# BPC_PWR.net
KiCad netlist of a schematic drawn in Altium Designer
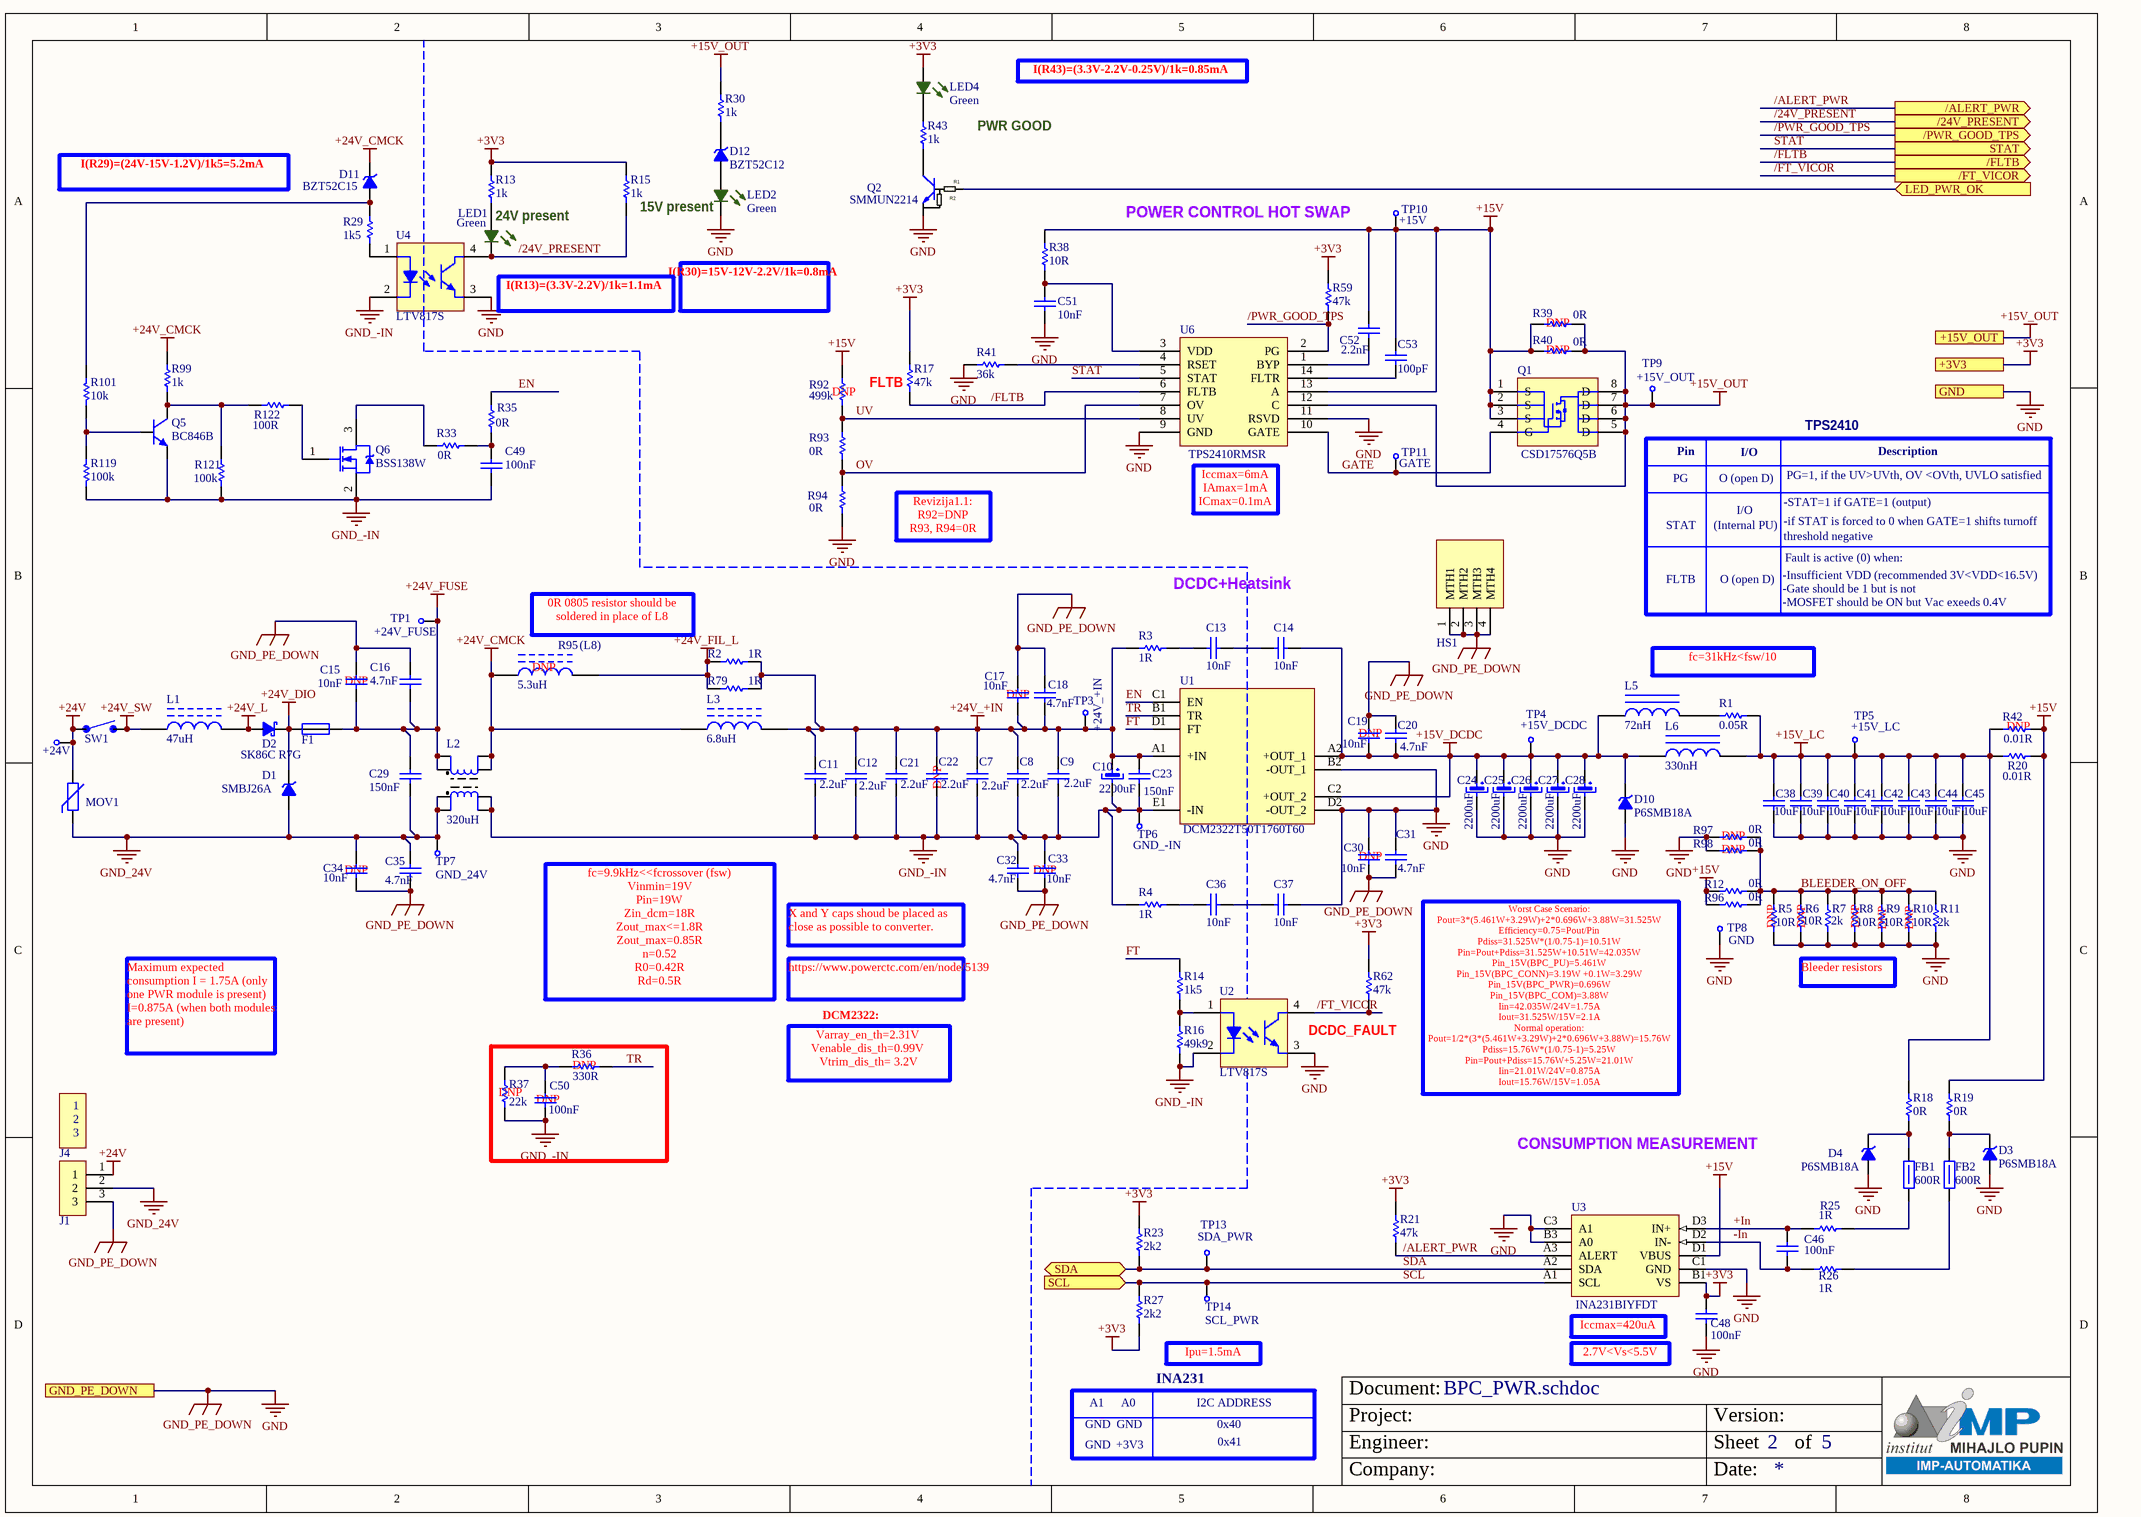
[diagram p0: BPC_PWR.schdoc]

(export (version "E")
  (design (tool "Eeschema 10.0.6"))
  (components
    (comp (ref "+24V")
      (value "Test Point Comment")
      (footprint "TP SMD 1.2mm MS")
      (description "Test Point SMD 1.2 mm No Via")
      (libsource (lib "MS IMP Library") (part "Test Point SMD"))
    )
    (comp (ref "C7")
      (value "Ceramic Capacitor")
      (footprint "2220 C 2.8MM MS")
      (description "Ceramic Capacitor 2.2uF 100V X6S 2220")
      (fields
        (field (name "DISTRIBUTOR PART NUMBER") "445-7781-1-ND")
        (field (name "MANUFACTURER") "TDK Corporation")
        (field (name "CAPACITANCE") "2.2uF")
      )
      (libsource (lib "MS IMP Library") (part "Cap Cer 2.2uF 450V X7R 2220 MS"))
    )
    (comp (ref "C8")
      (value "Ceramic Capacitor")
      (footprint "2220 C 2.8MM MS")
      (description "Ceramic Capacitor 2.2uF 100V X6S 2220")
      (fields
        (field (name "DISTRIBUTOR PART NUMBER") "445-7781-1-ND")
        (field (name "MANUFACTURER") "TDK Corporation")
        (field (name "CAPACITANCE") "2.2uF")
      )
      (libsource (lib "MS IMP Library") (part "Cap Cer 2.2uF 450V X7R 2220 MS"))
    )
    (comp (ref "C9")
      (value "Ceramic Capacitor")
      (footprint "2220 C 2.8MM MS")
      (description "Ceramic Capacitor 2.2uF 100V X6S 2220")
      (fields
        (field (name "DISTRIBUTOR PART NUMBER") "445-7781-1-ND")
        (field (name "MANUFACTURER") "TDK Corporation")
        (field (name "CAPACITANCE") "2.2uF")
      )
      (libsource (lib "MS IMP Library") (part "Cap Cer 2.2uF 450V X7R 2220 MS"))
    )
    (comp (ref "C10")
      (value "Electorlytic Capacitor")
      (footprint "CAPPRD750W85D1800H2000 MS")
      (description "Electorlytic Capacitor 2200uF 35V 18x20mm MS")
      (fields
        (field (name "DISTRIBUTOR PART NUMBER") "493-15957-ND")
        (field (name "MANUFACTURER") "Nichicon")
        (field (name "CAPACITANCE") "2200uF")
      )
      (libsource (lib "MS IMP Library") (part "Cap El 2200uF 35V 18x20mm MS"))
    )
    (comp (ref "C11")
      (value "Ceramic Capacitor")
      (footprint "2220 C 2.8MM MS")
      (description "Ceramic Capacitor 2.2uF 100V X6S 2220")
      (fields
        (field (name "DISTRIBUTOR PART NUMBER") "445-7781-1-ND")
        (field (name "MANUFACTURER") "TDK Corporation")
        (field (name "CAPACITANCE") "2.2uF")
      )
      (libsource (lib "MS IMP Library") (part "Cap Cer 2.2uF 450V X7R 2220 MS"))
    )
    (comp (ref "C12")
      (value "Ceramic Capacitor")
      (footprint "2220 C 2.8MM MS")
      (description "Ceramic Capacitor 2.2uF 100V X6S 2220")
      (fields
        (field (name "DISTRIBUTOR PART NUMBER") "445-7781-1-ND")
        (field (name "MANUFACTURER") "TDK Corporation")
        (field (name "CAPACITANCE") "2.2uF")
      )
      (libsource (lib "MS IMP Library") (part "Cap Cer 2.2uF 450V X7R 2220 MS"))
    )
    (comp (ref "C13")
      (value "Ceramic Capacitor")
      (footprint "1812 C 2.0MM MS")
      (description "Ceramic Capacitor 10nF 2kV X7R 1812")
      (fields
        (field (name "DISTRIBUTOR PART NUMBER") "399-10477-1-ND")
        (field (name "MANUFACTURER") "KEMET")
        (field (name "CAPACITANCE") "10nF")
      )
      (libsource (lib "MS IMP Library") (part "Cap Cer 10nF 2kV X7R 1812 MS"))
    )
    (comp (ref "C14")
      (value "Ceramic Capacitor")
      (footprint "1812 C 2.0MM MS")
      (description "Ceramic Capacitor 10nF 2kV X7R 1812")
      (fields
        (field (name "DISTRIBUTOR PART NUMBER") "399-10477-1-ND")
        (field (name "MANUFACTURER") "KEMET")
        (field (name "CAPACITANCE") "10nF")
      )
      (libsource (lib "MS IMP Library") (part "Cap Cer 10nF 2kV X7R 1812 MS"))
    )
    (comp (ref "C15")
      (value "Capacitor Y2")
      (footprint "R46KI21000001M")
      (description "Capacitor Y2 10nF 275V Polypropylene")
      (fields
        (field (name "DISTRIBUTOR PART NUMBER") "399-19749-ND")
        (field (name "MANUFACTURER") "Kemet")
        (field (name "POPULATED") "DNP")
        (field (name "DB PARAMETER 1") "10nF")
      )
      (libsource (lib "MS IMP Library") (part "Cap Y2 10nF 275V Polypropylene  MS"))
    )
    (comp (ref "C16")
      (value "Capacitor Y2")
      (footprint "R60QF14704001K")
      (description "Capacitor Y2 4.7nF 250V PET")
      (fields
        (field (name "DISTRIBUTOR PART NUMBER") "399-18570-ND")
        (field (name "MANUFACTURER") "Kemet")
        (field (name "DB PARAMETER 1") "4.7nF")
      )
      (libsource (lib "MS IMP Library") (part "Cap Y2 4.7nF 250V PET MS"))
    )
    (comp (ref "C17")
      (value "Capacitor Y2")
      (footprint "R46KI21000001M")
      (description "Capacitor Y2 10nF 275V Polypropylene")
      (fields
        (field (name "DISTRIBUTOR PART NUMBER") "399-19749-ND")
        (field (name "MANUFACTURER") "Kemet")
        (field (name "POPULATED") "DNP")
        (field (name "DB PARAMETER 1") "10nF")
      )
      (libsource (lib "MS IMP Library") (part "Cap Y2 10nF 275V Polypropylene  MS"))
    )
    (comp (ref "C18")
      (value "Capacitor Y2")
      (footprint "R60QF14704001K")
      (description "Capacitor Y2 4.7nF 250V PET")
      (fields
        (field (name "DISTRIBUTOR PART NUMBER") "399-18570-ND")
        (field (name "MANUFACTURER") "Kemet")
        (field (name "DB PARAMETER 1") "4.7nF")
      )
      (libsource (lib "MS IMP Library") (part "Cap Y2 4.7nF 250V PET MS"))
    )
    (comp (ref "C19")
      (value "Capacitor Y2")
      (footprint "R46KI21000001M")
      (description "Capacitor Y2 10nF 275V Polypropylene")
      (fields
        (field (name "DISTRIBUTOR PART NUMBER") "399-19749-ND")
        (field (name "MANUFACTURER") "Kemet")
        (field (name "POPULATED") "DNP")
        (field (name "DB PARAMETER 1") "10nF")
      )
      (libsource (lib "MS IMP Library") (part "Cap Y2 10nF 275V Polypropylene  MS"))
    )
    (comp (ref "C20")
      (value "Capacitor Y2")
      (footprint "R60QF14704001K")
      (description "Capacitor Y2 4.7nF 250V PET")
      (fields
        (field (name "DISTRIBUTOR PART NUMBER") "399-18570-ND")
        (field (name "MANUFACTURER") "Kemet")
        (field (name "DB PARAMETER 1") "4.7nF")
      )
      (libsource (lib "MS IMP Library") (part "Cap Y2 4.7nF 250V PET MS"))
    )
    (comp (ref "C21")
      (value "Ceramic Capacitor")
      (footprint "2220 C 2.8MM MS")
      (description "Ceramic Capacitor 2.2uF 100V X6S 2220")
      (fields
        (field (name "DISTRIBUTOR PART NUMBER") "445-7781-1-ND")
        (field (name "MANUFACTURER") "TDK Corporation")
        (field (name "CAPACITANCE") "2.2uF")
      )
      (libsource (lib "MS IMP Library") (part "Cap Cer 2.2uF 450V X7R 2220 MS"))
    )
    (comp (ref "C22")
      (value "Ceramic Capacitor")
      (footprint "2220 C 2.8MM MS")
      (description "Ceramic Capacitor 2.2uF 100V X6S 2220")
      (fields
        (field (name "DISTRIBUTOR PART NUMBER") "445-7781-1-ND")
        (field (name "MANUFACTURER") "TDK Corporation")
        (field (name "POPULATED") "DNP")
        (field (name "CAPACITANCE") "2.2uF")
      )
      (libsource (lib "MS IMP Library") (part "Cap Cer 2.2uF 450V X7R 2220 MS"))
    )
    (comp (ref "C23")
      (value "Capacitor X2")
      (footprint "MKX2 6mmx18mmx12.5mm")
      (description "Capacitor X2 150nF 305V PP")
      (fields
        (field (name "DISTRIBUTOR PART NUMBER") "505-MKX2AW31504C00KI")
        (field (name "MANUFACTURER") "WIMA")
        (field (name "DB PARAMETER 1") "150nF")
      )
      (libsource (lib "MS IMP Library") (part "Cap X2 150nF 305V PP MS"))
    )
    (comp (ref "C24")
      (value "Electorlytic Capacitor")
      (footprint "CAPPRD750W85D1800H2000 MS")
      (description "Electorlytic Capacitor 2200uF 35V 18x20mm MS")
      (fields
        (field (name "DISTRIBUTOR PART NUMBER") "493-15957-ND")
        (field (name "MANUFACTURER") "Nichicon")
        (field (name "CAPACITANCE") "2200uF")
      )
      (libsource (lib "MS IMP Library") (part "Cap El 2200uF 35V 18x20mm MS"))
    )
    (comp (ref "C25")
      (value "Electorlytic Capacitor")
      (footprint "CAPPRD750W85D1800H2000 MS")
      (description "Electorlytic Capacitor 2200uF 35V 18x20mm MS")
      (fields
        (field (name "DISTRIBUTOR PART NUMBER") "493-15957-ND")
        (field (name "MANUFACTURER") "Nichicon")
        (field (name "CAPACITANCE") "2200uF")
      )
      (libsource (lib "MS IMP Library") (part "Cap El 2200uF 35V 18x20mm MS"))
    )
    (comp (ref "C26")
      (value "Electorlytic Capacitor")
      (footprint "CAPPRD750W85D1800H2000 MS")
      (description "Electorlytic Capacitor 2200uF 35V 18x20mm MS")
      (fields
        (field (name "DISTRIBUTOR PART NUMBER") "493-15957-ND")
        (field (name "MANUFACTURER") "Nichicon")
        (field (name "CAPACITANCE") "2200uF")
      )
      (libsource (lib "MS IMP Library") (part "Cap El 2200uF 35V 18x20mm MS"))
    )
    (comp (ref "C27")
      (value "Electorlytic Capacitor")
      (footprint "CAPPRD750W85D1800H2000 MS")
      (description "Electorlytic Capacitor 2200uF 35V 18x20mm MS")
      (fields
        (field (name "DISTRIBUTOR PART NUMBER") "493-15957-ND")
        (field (name "MANUFACTURER") "Nichicon")
        (field (name "CAPACITANCE") "2200uF")
      )
      (libsource (lib "MS IMP Library") (part "Cap El 2200uF 35V 18x20mm MS"))
    )
    (comp (ref "C28")
      (value "Electorlytic Capacitor")
      (footprint "CAPPRD750W85D1800H2000 MS")
      (description "Electorlytic Capacitor 2200uF 35V 18x20mm MS")
      (fields
        (field (name "DISTRIBUTOR PART NUMBER") "493-15957-ND")
        (field (name "MANUFACTURER") "Nichicon")
        (field (name "CAPACITANCE") "2200uF")
      )
      (libsource (lib "MS IMP Library") (part "Cap El 2200uF 35V 18x20mm MS"))
    )
    (comp (ref "C29")
      (value "Capacitor X2")
      (footprint "MKX2 6mmx18mmx12.5mm")
      (description "Capacitor X2 150nF 305V PP")
      (fields
        (field (name "DISTRIBUTOR PART NUMBER") "505-MKX2AW31504C00KI")
        (field (name "MANUFACTURER") "WIMA")
        (field (name "DB PARAMETER 1") "150nF")
      )
      (libsource (lib "MS IMP Library") (part "Cap X2 150nF 305V PP MS"))
    )
    (comp (ref "C30")
      (value "Capacitor Y2")
      (footprint "R46KI21000001M")
      (description "Capacitor Y2 10nF 275V Polypropylene")
      (fields
        (field (name "DISTRIBUTOR PART NUMBER") "399-19749-ND")
        (field (name "MANUFACTURER") "Kemet")
        (field (name "POPULATED") "DNP")
        (field (name "DB PARAMETER 1") "10nF")
      )
      (libsource (lib "MS IMP Library") (part "Cap Y2 10nF 275V Polypropylene  MS"))
    )
    (comp (ref "C31")
      (value "Capacitor Y2")
      (footprint "R60QF14704001K")
      (description "Capacitor Y2 4.7nF 250V PET")
      (fields
        (field (name "DISTRIBUTOR PART NUMBER") "399-18570-ND")
        (field (name "MANUFACTURER") "Kemet")
        (field (name "DB PARAMETER 1") "4.7nF")
      )
      (libsource (lib "MS IMP Library") (part "Cap Y2 4.7nF 250V PET MS"))
    )
    (comp (ref "C32")
      (value "Capacitor Y2")
      (footprint "R60QF14704001K")
      (description "Capacitor Y2 4.7nF 250V PET")
      (fields
        (field (name "DISTRIBUTOR PART NUMBER") "399-18570-ND")
        (field (name "MANUFACTURER") "Kemet")
        (field (name "DB PARAMETER 1") "4.7nF")
      )
      (libsource (lib "MS IMP Library") (part "Cap Y2 4.7nF 250V PET MS"))
    )
    (comp (ref "C33")
      (value "Capacitor Y2")
      (footprint "R46KI21000001M")
      (description "Capacitor Y2 10nF 275V Polypropylene")
      (fields
        (field (name "DISTRIBUTOR PART NUMBER") "399-19749-ND")
        (field (name "MANUFACTURER") "Kemet")
        (field (name "POPULATED") "DNP")
        (field (name "DB PARAMETER 1") "10nF")
      )
      (libsource (lib "MS IMP Library") (part "Cap Y2 10nF 275V Polypropylene  MS"))
    )
    (comp (ref "C34")
      (value "Capacitor Y2")
      (footprint "R46KI21000001M")
      (description "Capacitor Y2 10nF 275V Polypropylene")
      (fields
        (field (name "DISTRIBUTOR PART NUMBER") "399-19749-ND")
        (field (name "MANUFACTURER") "Kemet")
        (field (name "POPULATED") "DNP")
        (field (name "DB PARAMETER 1") "10nF")
      )
      (libsource (lib "MS IMP Library") (part "Cap Y2 10nF 275V Polypropylene  MS"))
    )
    (comp (ref "C35")
      (value "Capacitor Y2")
      (footprint "R60QF14704001K")
      (description "Capacitor Y2 4.7nF 250V PET")
      (fields
        (field (name "DISTRIBUTOR PART NUMBER") "399-18570-ND")
        (field (name "MANUFACTURER") "Kemet")
        (field (name "DB PARAMETER 1") "4.7nF")
      )
      (libsource (lib "MS IMP Library") (part "Cap Y2 4.7nF 250V PET MS"))
    )
    (comp (ref "C36")
      (value "Ceramic Capacitor")
      (footprint "1812 C 2.0MM MS")
      (description "Ceramic Capacitor 10nF 2kV X7R 1812")
      (fields
        (field (name "DISTRIBUTOR PART NUMBER") "399-10477-1-ND")
        (field (name "MANUFACTURER") "KEMET")
        (field (name "CAPACITANCE") "10nF")
      )
      (libsource (lib "MS IMP Library") (part "Cap Cer 10nF 2kV X7R 1812 MS"))
    )
    (comp (ref "C37")
      (value "Ceramic Capacitor")
      (footprint "1812 C 2.0MM MS")
      (description "Ceramic Capacitor 10nF 2kV X7R 1812")
      (fields
        (field (name "DISTRIBUTOR PART NUMBER") "399-10477-1-ND")
        (field (name "MANUFACTURER") "KEMET")
        (field (name "CAPACITANCE") "10nF")
      )
      (libsource (lib "MS IMP Library") (part "Cap Cer 10nF 2kV X7R 1812 MS"))
    )
    (comp (ref "C38")
      (value "Ceramic Capacitor")
      (footprint "2220 C 2.8MM MS")
      (description "Ceramic Capacitor 10uF 100V X7S 2220")
      (fields
        (field (name "DISTRIBUTOR PART NUMBER") "445-13408-1-ND")
        (field (name "MANUFACTURER") "TDK Corporation")
        (field (name "CAPACITANCE") "10uF")
      )
      (libsource (lib "MS IMP Library") (part "Cap Cer 10uF 100V X7S 2220 MS"))
    )
    (comp (ref "C39")
      (value "Ceramic Capacitor")
      (footprint "2220 C 2.8MM MS")
      (description "Ceramic Capacitor 10uF 100V X7S 2220")
      (fields
        (field (name "DISTRIBUTOR PART NUMBER") "445-13408-1-ND")
        (field (name "MANUFACTURER") "TDK Corporation")
        (field (name "CAPACITANCE") "10uF")
      )
      (libsource (lib "MS IMP Library") (part "Cap Cer 10uF 100V X7S 2220 MS"))
    )
    (comp (ref "C40")
      (value "Ceramic Capacitor")
      (footprint "2220 C 2.8MM MS")
      (description "Ceramic Capacitor 10uF 100V X7S 2220")
      (fields
        (field (name "DISTRIBUTOR PART NUMBER") "445-13408-1-ND")
        (field (name "MANUFACTURER") "TDK Corporation")
        (field (name "CAPACITANCE") "10uF")
      )
      (libsource (lib "MS IMP Library") (part "Cap Cer 10uF 100V X7S 2220 MS"))
    )
    (comp (ref "C41")
      (value "Ceramic Capacitor")
      (footprint "2220 C 2.8MM MS")
      (description "Ceramic Capacitor 10uF 100V X7S 2220")
      (fields
        (field (name "DISTRIBUTOR PART NUMBER") "445-13408-1-ND")
        (field (name "MANUFACTURER") "TDK Corporation")
        (field (name "CAPACITANCE") "10uF")
      )
      (libsource (lib "MS IMP Library") (part "Cap Cer 10uF 100V X7S 2220 MS"))
    )
    (comp (ref "C42")
      (value "Ceramic Capacitor")
      (footprint "2220 C 2.8MM MS")
      (description "Ceramic Capacitor 10uF 100V X7S 2220")
      (fields
        (field (name "DISTRIBUTOR PART NUMBER") "445-13408-1-ND")
        (field (name "MANUFACTURER") "TDK Corporation")
        (field (name "CAPACITANCE") "10uF")
      )
      (libsource (lib "MS IMP Library") (part "Cap Cer 10uF 100V X7S 2220 MS"))
    )
    (comp (ref "C43")
      (value "Ceramic Capacitor")
      (footprint "2220 C 2.8MM MS")
      (description "Ceramic Capacitor 10uF 100V X7S 2220")
      (fields
        (field (name "DISTRIBUTOR PART NUMBER") "445-13408-1-ND")
        (field (name "MANUFACTURER") "TDK Corporation")
        (field (name "CAPACITANCE") "10uF")
      )
      (libsource (lib "MS IMP Library") (part "Cap Cer 10uF 100V X7S 2220 MS"))
    )
    (comp (ref "C44")
      (value "Ceramic Capacitor")
      (footprint "2220 C 2.8MM MS")
      (description "Ceramic Capacitor 10uF 100V X7S 2220")
      (fields
        (field (name "DISTRIBUTOR PART NUMBER") "445-13408-1-ND")
        (field (name "MANUFACTURER") "TDK Corporation")
        (field (name "CAPACITANCE") "10uF")
      )
      (libsource (lib "MS IMP Library") (part "Cap Cer 10uF 100V X7S 2220 MS"))
    )
    (comp (ref "C45")
      (value "Ceramic Capacitor")
      (footprint "2220 C 2.8MM MS")
      (description "Ceramic Capacitor 10uF 100V X7S 2220")
      (fields
        (field (name "DISTRIBUTOR PART NUMBER") "445-13408-1-ND")
        (field (name "MANUFACTURER") "TDK Corporation")
        (field (name "CAPACITANCE") "10uF")
      )
      (libsource (lib "MS IMP Library") (part "Cap Cer 10uF 100V X7S 2220 MS"))
    )
    (comp (ref "C46")
      (value "Ceramic Capacitor")
      (footprint "C0603L 0.8 MM MS")
      (description "Ceramic Capacitor 100nF 50V X7R 0603")
      (fields
        (field (name "DISTRIBUTOR PART NUMBER") "187-CL10B104KB8WPNC")
        (field (name "MANUFACTURER") "Samsung Electro-Mechanics")
        (field (name "CAPACITANCE") "100nF")
      )
      (libsource (lib "MS IMP Library") (part "Cap Cer 100nF 50V X7R 0603 Pt02"))
    )
    (comp (ref "C48")
      (value "Ceramic Capacitor")
      (footprint "C0603L 0.8 MM MS")
      (description "Ceramic Capacitor 100nF 50V X7R 0603")
      (fields
        (field (name "DISTRIBUTOR PART NUMBER") "187-CL10B104KB8WPNC")
        (field (name "MANUFACTURER") "Samsung Electro-Mechanics")
        (field (name "CAPACITANCE") "100nF")
      )
      (libsource (lib "MS IMP Library") (part "Cap Cer 100nF 50V X7R 0603 Pt02"))
    )
    (comp (ref "C49")
      (value "Ceramic Capacitor")
      (footprint "C0603L 0.8 MM MS")
      (description "Ceramic Capacitor 100nF 50V X7R 0603")
      (fields
        (field (name "DISTRIBUTOR PART NUMBER") "187-CL10B104KB8WPNC")
        (field (name "MANUFACTURER") "Samsung Electro-Mechanics")
        (field (name "CAPACITANCE") "100nF")
      )
      (libsource (lib "MS IMP Library") (part "Cap Cer 100nF 50V X7R 0603 Pt02"))
    )
    (comp (ref "C50")
      (value "Ceramic Capacitor")
      (footprint "C0603L 0.8 MM MS")
      (description "Ceramic Capacitor 100nF 50V X7R 0603")
      (fields
        (field (name "DISTRIBUTOR PART NUMBER") "187-CL10B104KB8WPNC")
        (field (name "MANUFACTURER") "Samsung Electro-Mechanics")
        (field (name "PRODUCTION STATUS") "DNP")
        (field (name "CAPACITANCE") "100nF")
      )
      (libsource (lib "MS IMP Library") (part "Cap Cer 100nF 50V X7R 0603 Pt02"))
    )
    (comp (ref "C51")
      (value "Ceramic Capacitor")
      (footprint "C0603L 0.8 MM MS")
      (description "Ceramic Capacitor 10nF 50V X7R 0603")
      (fields
        (field (name "DISTRIBUTOR PART NUMBER") "445-5662-1-ND")
        (field (name "MANUFACTURER") "TDK Corporation")
        (field (name "CAPACITANCE") "10nF")
      )
      (libsource (lib "MS IMP Library") (part "Cap Cer 10nF 50V X7R 0603 MS"))
    )
    (comp (ref "C52")
      (value "Ceramic Capacitor")
      (footprint "C0603L 0.8 MM MS")
      (description "Ceramic Capacitor 2.2nF 100V X7R 0603")
      (fields
        (field (name "DISTRIBUTOR PART NUMBER") "445-5808-1-ND")
        (field (name "MANUFACTURER") "TDK Corporation")
        (field (name "CAPACITANCE") "2.2nF")
      )
      (libsource (lib "MS IMP Library") (part "Cap Cer 2.2nF 100V X7R 0603 MS"))
    )
    (comp (ref "C53")
      (value "Ceramic Capacitor")
      (footprint "C0603L 0.8 MM MS")
      (description "Ceramic Capacitor 100pF 100V X7R 0603")
      (fields
        (field (name "DISTRIBUTOR PART NUMBER") "478-12671-1-ND")
        (field (name "MANUFACTURER") "AVX Corporation")
        (field (name "CAPACITANCE") "100pF")
      )
      (libsource (lib "MS IMP Library") (part "Cap Cer 100pF 100V X7R 0603 MS"))
    )
    (comp (ref "D1")
      (value "SMBJ26A")
      (footprint "DO-214AA SMB MS")
      (description "TVS Diode 26V 600W Unidirectional")
      (fields (field (name "DISTRIBUTOR PART NUMBER") "SMBJ26ABCT-ND") (field (name "MANUFACTURER") "Bourns"))
      (libsource (lib "MS IMP Library") (part "Dio TVS Udir 26V 600W SMBJ26A MS"))
    )
    (comp (ref "D2")
      (value "SK86C R7G")
      (footprint "DIOM7959X262N")
      (description "Schottky Diode 8A 60V SMC")
      (fields
        (field (name "DISTRIBUTOR PART NUMBER") "SK86CR7GCT-ND")
        (field (name "MANUFACTURER") "Taiwan Semiconductor Corporation")
      )
      (libsource (lib "MS IMP Library") (part "Dio Sch 8A 60V SMC MS"))
    )
    (comp (ref "D3")
      (value "P6SMB18A")
      (footprint "DO-214AA SMB MS")
      (description "TVS Diode 15.3V 600W Unidirectional")
      (fields
        (field (name "DISTRIBUTOR PART NUMBER") "P6SMB18ABBCT-ND")
        (field (name "MANUFACTURER") "Bourns")
      )
      (libsource (lib "MS IMP Library") (part "Dio TVS Udir 15.3V 600W P6SMB18A MS"))
    )
    (comp (ref "D4")
      (value "P6SMB18A")
      (footprint "DO-214AA SMB MS")
      (description "TVS Diode 15.3V 600W Unidirectional")
      (fields
        (field (name "DISTRIBUTOR PART NUMBER") "P6SMB18ABBCT-ND")
        (field (name "MANUFACTURER") "Bourns")
      )
      (libsource (lib "MS IMP Library") (part "Dio TVS Udir 15.3V 600W P6SMB18A MS"))
    )
    (comp (ref "D10")
      (value "P6SMB18A")
      (footprint "DO-214AA SMB MS")
      (description "TVS Diode 15.3V 600W Unidirectional")
      (fields
        (field (name "DISTRIBUTOR PART NUMBER") "P6SMB18ABBCT-ND")
        (field (name "MANUFACTURER") "Bourns")
      )
      (libsource (lib "MS IMP Library") (part "Dio TVS Udir 15.3V 600W P6SMB18A MS"))
    )
    (comp (ref "D11")
      (value "BZT52C15")
      (footprint "SOD-123 MS")
      (description "Zener Diode 15V 500mW")
      (fields
        (field (name "DISTRIBUTOR PART NUMBER") "637-BZT52C15")
        (field (name "MANUFACTURER") "Diotec Semiconductor")
      )
      (libsource (lib "MS IMP Library") (part "Dio Zen 15V 500mW BZT52C15S  MS"))
    )
    (comp (ref "D12")
      (value "BZT52C12")
      (footprint "SOD-123 MS")
      (description "Zener Diode 12V 500mW")
      (fields
        (field (name "DISTRIBUTOR PART NUMBER") "621-BZT52C12-F")
        (field (name "MANUFACTURER") "Diodes Inc.")
      )
      (libsource (lib "MS IMP Library") (part "Dio Zen 12V 500mW BZT52C12 MS"))
    )
    (comp (ref "F1")
      (value "FUSEHOLDER")
      (footprint "FUSEHOLDER_00318221")
      (description "FUSEHOLDER 10A 500V")
      (fields
        (field (name "DISTRIBUTOR PART NUMBER") "486-1260-ND")
        (field (name "MANUFACTURER") "Schurter Inc.")
      )
      (libsource (lib "MS IMP Library") (part "FUSEHOLDER"))
    )
    (comp (ref "FB1")
      (value "Ferrite Bead")
      (footprint "0805 FB 0.85mm MS")
      (description "Ferrite Bead 2A 600R@100MHz 0805")
      (fields
        (field (name "DISTRIBUTOR PART NUMBER") "490-18588-1-ND")
        (field (name "MANUFACTURER") "Murata Electronics")
        (field (name "IMPEDANCE @ 100MHZ") "600R")
      )
      (libsource (lib "MS IMP Library") (part "FB 2A 600R 0805 Pt02 MS"))
    )
    (comp (ref "FB2")
      (value "Ferrite Bead")
      (footprint "0805 FB 0.85mm MS")
      (description "Ferrite Bead 2A 600R@100MHz 0805")
      (fields
        (field (name "DISTRIBUTOR PART NUMBER") "490-18588-1-ND")
        (field (name "MANUFACTURER") "Murata Electronics")
        (field (name "IMPEDANCE @ 100MHZ") "600R")
      )
      (libsource (lib "MS IMP Library") (part "FB 2A 600R 0805 Pt02 MS"))
    )
    (comp (ref "HS1")
      (value "Heatsink")
      (footprint "Heatsink VICOR Tranverse Grounding Tabs Thermal 40138")
      (description "Heatsink Vicor Transverse 40138")
      (fields (field (name "DISTRIBUTOR PART NUMBER") "40138") (field (name "MANUFACTURER") "Vicor"))
      (libsource (lib "MS IMP Library") (part "Mech Heatsink Vicor Transverse 40138"))
    )
    (comp (ref "J1")
      (value "Header Male TH 3-pin")
      (footprint "MSTB 2,5_3-GF-5,08 - 1776511")
      (description "Con Header 1x3 5.08 12A")
      (fields
        (field (name "DISTRIBUTOR PART NUMBER") "277-5772-ND")
        (field (name "MANUFACTURER") "Phoenix Contact")
      )
      (libsource (lib "MS IMP Library") (part "Con Header 1x3 5.08 Phoenix MS"))
    )
    (comp (ref "J4")
      (value "Header Male TH 3-pin")
      (footprint "MSTB 2,5/ 3-STF-5,08 - 1777992")
      (description "Con Header 1x3 5.08 12A")
      (fields
        (field (name "DISTRIBUTOR PART NUMBER") "277-5712-ND")
        (field (name "MANUFACTURER") "Phoenix Contact")
      )
      (libsource (lib "MS IMP Library") (part "Mech Con Cable 1x3 5.08 Phoenix MS"))
    )
    (comp (ref "L1")
      (value "Inductor")
      (footprint "SER1390153MLB")
      (description "Inductor 47uH 2.6A 2.31 MOHM")
      (fields
        (field (name "DISTRIBUTOR PART NUMBER") "994-SER1390-473MLB")
        (field (name "MANUFACTURER") "Coilcraft")
        (field (name "INDUCTANCE") "47uH")
      )
      (libsource (lib "MS IMP Library") (part "Ind  47uH 2.6A SER1390"))
    )
    (comp (ref "L2")
      (value "Inductor Common Mode Choke")
      (footprint "WE-UCF")
      (description "Inductor 320uH 3.25A 744290321")
      (fields
        (field (name "DISTRIBUTOR PART NUMBER") "732-5616-1-ND")
        (field (name "MANUFACTURER") "Würth Elektronik")
        (field (name "INDUCTANCE") "320uH")
      )
      (libsource (lib "MS IMP Library") (part "Ind CMC 320µH  3.25A 744290321 MS"))
    )
    (comp (ref "L3")
      (value "Inductor")
      (footprint "INDPM110100X400N_MSS1048")
      (description "Inductor 6.8uH 6.01A 15.4 MOHM")
      (fields
        (field (name "DISTRIBUTOR PART NUMBER") "994-MSS1048-682NLC")
        (field (name "MANUFACTURER") "Coilcraft")
        (field (name "INDUCTANCE") "6.8uH")
      )
      (libsource (lib "MS IMP Library") (part "Ind  6.8uH 6.01A MSS1048 MS"))
    )
    (comp (ref "L5")
      (value "Inductor")
      (footprint "IFLR2727")
      (description "Inductor 72nH 45A IFLR2727")
      (fields
        (field (name "DISTRIBUTOR PART NUMBER") "541-3104-1-ND")
        (field (name "MANUFACTURER") "Vishay Dale")
        (field (name "INDUCTANCE") "72nH")
      )
      (libsource (lib "MS IMP Library") (part "Ind 72nH 45A IFLR2727 MS"))
    )
    (comp (ref "L6")
      (value "Inductor")
      (footprint "IHLP3232")
      (description "Inductor 330nH 29.5A IHLP3232")
      (fields
        (field (name "DISTRIBUTOR PART NUMBER") "541-1379-1-ND")
        (field (name "MANUFACTURER") "Vishay Dale")
        (field (name "INDUCTANCE") "330nH")
      )
      (libsource (lib "MS IMP Library") (part "Ind 330nH 29.5A IHLP3232 MS"))
    )
    (comp (ref "LED1")
      (value "Green")
      (footprint "LED GRN Mentor 2632.8380 x1")
      (description "LED Mentor 2632.8320 GRN x1")
      (fields
        (field (name "DISTRIBUTOR PART NUMBER") "2632.8380")
        (field (name "MANUFACTURER") "Mentor")
        (field (name "LED COLOR") "Green")
      )
      (libsource (lib "MS IMP Library") (part "LED Mentor 2632.8380 GRN x1 MS"))
    )
    (comp (ref "LED2")
      (value "Green")
      (footprint "LED GRN Mentor 2632.8380 x1")
      (description "LED Mentor 2632.8320 GRN x1")
      (fields
        (field (name "DISTRIBUTOR PART NUMBER") "2632.8380")
        (field (name "MANUFACTURER") "Mentor")
        (field (name "LED COLOR") "Green")
      )
      (libsource (lib "MS IMP Library") (part "LED Mentor 2632.8380 GRN x1 MS"))
    )
    (comp (ref "LED4")
      (value "Green")
      (footprint "LED GRN Mentor 2632.8380 x1")
      (description "LED Mentor 2632.8320 GRN x1")
      (fields
        (field (name "DISTRIBUTOR PART NUMBER") "2632.8380")
        (field (name "MANUFACTURER") "Mentor")
        (field (name "LED COLOR") "Green")
      )
      (libsource (lib "MS IMP Library") (part "LED Mentor 2632.8380 GRN x1 MS"))
    )
    (comp (ref "MOV1")
      (value "Varistor")
      (footprint "MOV10D470K")
      (description "Varistor 47V 500A DISC 10MM")
      (fields
        (field (name "DISTRIBUTOR PART NUMBER") "MOV-10D470KTRCT-ND")
        (field (name "MANUFACTURER") "Bourns Inc.")
      )
      (libsource (lib "MS IMP Library") (part "MOV 47V 5.5J 10D470K"))
    )
    (comp (ref "Q1")
      (value "CSD17576Q5B")
      (footprint "DNK8 MS")
      (description "MOSFET N-CH 30V 100A 8VSON")
      (fields
        (field (name "DISTRIBUTOR PART NUMBER") "296-43635-1-ND")
        (field (name "MANUFACTURER") "Texas Instruments")
      )
      (libsource (lib "MS IMP Library") (part "Tr CSD17576Q5B MS"))
    )
    (comp (ref "Q2")
      (value "SMMUN2214")
      (footprint "SOT-23 MS")
      (description "TRANS PREBIAS NPN 50V SOT23")
      (fields
        (field (name "DISTRIBUTOR PART NUMBER") "SMMUN2214LT1GOSCT-ND")
        (field (name "MANUFACTURER") "ON Semiconductor")
      )
      (libsource (lib "MS IMP Library") (part "Tra NPN Prebias MS"))
    )
    (comp (ref "Q5")
      (value "BC846B")
      (footprint "SOT-23 NXP MS")
      (description "65V, 100mA NPN general-purpose transistor")
      (fields
        (field (name "DISTRIBUTOR PART NUMBER") "771-BC846B-T/R")
        (field (name "MANUFACTURER") "Nexperia")
      )
      (libsource (lib "MS IMP Library") (part "Tra NPN BC846B MS"))
    )
    (comp (ref "Q6")
      (value "BSS138W")
      (footprint "SOT65P210X110-3N")
      (description "MOSFET N-CH 50V 210MA SC70")
      (fields
        (field (name "DISTRIBUTOR PART NUMBER") "BSS138WCT-ND")
        (field (name "MANUFACTURER") "ON Semiconductor")
      )
      (libsource (lib "MS IMP Library") (part "Tra N-CH BSS138W MS"))
    )
    (comp (ref "R1")
      (value "Resistor")
      (footprint "2512 R 0.7mm MS")
      (description "Resistor 0.05R 1% 1W 2512")
      (fields
        (field (name "DISTRIBUTOR PART NUMBER") "311-0.05TCT-ND")
        (field (name "MANUFACTURER") "Yageo")
        (field (name "RESISTANCE") "0.05R")
      )
      (libsource (lib "MS IMP Library") (part "Res 0.05R 1% 1W 2512 MS"))
    )
    (comp (ref "R2")
      (value "Resistor")
      (footprint "2512 R 0.7mm MS")
      (description "Resistor 1R 5% 1W 2512")
      (fields
        (field (name "DISTRIBUTOR PART NUMBER") "2019-SR733ATTE1R00FCT-ND")
        (field (name "MANUFACTURER") "KOA Speer Electronics, Inc.")
        (field (name "RESISTANCE") "1R")
      )
      (libsource (lib "MS IMP Library") (part "Res 1R 5% 1W 2512 MS"))
    )
    (comp (ref "R3")
      (value "Resistor")
      (footprint "2512 R 0.7mm MS")
      (description "Resistor 1R 5% 1W 2512")
      (fields
        (field (name "DISTRIBUTOR PART NUMBER") "2019-SR733ATTE1R00FCT-ND")
        (field (name "MANUFACTURER") "KOA Speer Electronics, Inc.")
        (field (name "RESISTANCE") "1R")
      )
      (libsource (lib "MS IMP Library") (part "Res 1R 5% 1W 2512 MS"))
    )
    (comp (ref "R4")
      (value "Resistor")
      (footprint "2512 R 0.7mm MS")
      (description "Resistor 1R 5% 1W 2512")
      (fields
        (field (name "DISTRIBUTOR PART NUMBER") "2019-SR733ATTE1R00FCT-ND")
        (field (name "MANUFACTURER") "KOA Speer Electronics, Inc.")
        (field (name "RESISTANCE") "1R")
      )
      (libsource (lib "MS IMP Library") (part "Res 1R 5% 1W 2512 MS"))
    )
    (comp (ref "R5")
      (value "Resistor")
      (footprint "2512 R 0.7mm MS")
      (description "Resistor 10R 5% 2W 2512 MS")
      (fields
        (field (name "DISTRIBUTOR PART NUMBER") "YAG5928CT-ND")
        (field (name "MANUFACTURER") "Yageo")
        (field (name "POPULATED") "DNP")
        (field (name "RESISTANCE") "10R")
      )
      (libsource (lib "MS IMP Library") (part "Res 10R 5% 2W 2512 MS"))
    )
    (comp (ref "R6")
      (value "Resistor")
      (footprint "2512 R 0.7mm MS")
      (description "Resistor 10R 5% 2W 2512 MS")
      (fields
        (field (name "DISTRIBUTOR PART NUMBER") "YAG5928CT-ND")
        (field (name "MANUFACTURER") "Yageo")
        (field (name "POPULATED") "DNP")
        (field (name "RESISTANCE") "10R")
      )
      (libsource (lib "MS IMP Library") (part "Res 10R 5% 2W 2512 MS"))
    )
    (comp (ref "R7")
      (value "Resistor")
      (footprint "2512 R 0.7mm MS")
      (description "Resistor 2k 1% 2W 2512 MS")
      (fields
        (field (name "DISTRIBUTOR PART NUMBER") "279-35212K0FT")
        (field (name "MANUFACTURER") "TE Connectivity / Holsworthy")
        (field (name "RESISTANCE") "2k")
      )
      (libsource (lib "MS IMP Library") (part "Res 2k 1% 2W 2512 MS"))
    )
    (comp (ref "R8")
      (value "Resistor")
      (footprint "2512 R 0.7mm MS")
      (description "Resistor 10R 5% 2W 2512 MS")
      (fields
        (field (name "DISTRIBUTOR PART NUMBER") "YAG5928CT-ND")
        (field (name "MANUFACTURER") "Yageo")
        (field (name "POPULATED") "DNP")
        (field (name "RESISTANCE") "10R")
      )
      (libsource (lib "MS IMP Library") (part "Res 10R 5% 2W 2512 MS"))
    )
    (comp (ref "R9")
      (value "Resistor")
      (footprint "2512 R 0.7mm MS")
      (description "Resistor 10R 5% 2W 2512 MS")
      (fields
        (field (name "DISTRIBUTOR PART NUMBER") "YAG5928CT-ND")
        (field (name "MANUFACTURER") "Yageo")
        (field (name "POPULATED") "DNP")
        (field (name "RESISTANCE") "10R")
      )
      (libsource (lib "MS IMP Library") (part "Res 10R 5% 2W 2512 MS"))
    )
    (comp (ref "R10")
      (value "Resistor")
      (footprint "2512 R 0.7mm MS")
      (description "Resistor 10R 5% 2W 2512 MS")
      (fields
        (field (name "DISTRIBUTOR PART NUMBER") "YAG5928CT-ND")
        (field (name "MANUFACTURER") "Yageo")
        (field (name "POPULATED") "DNP")
        (field (name "RESISTANCE") "10R")
      )
      (libsource (lib "MS IMP Library") (part "Res 10R 5% 2W 2512 MS"))
    )
    (comp (ref "R11")
      (value "Resistor")
      (footprint "2512 R 0.7mm MS")
      (description "Resistor 2k 1% 2W 2512 MS")
      (fields
        (field (name "DISTRIBUTOR PART NUMBER") "279-35212K0FT")
        (field (name "MANUFACTURER") "TE Connectivity / Holsworthy")
        (field (name "RESISTANCE") "2k")
      )
      (libsource (lib "MS IMP Library") (part "Res 2k 1% 2W 2512 MS"))
    )
    (comp (ref "R12")
      (value "Resistor")
      (footprint "R0603L 0.45MM MS")
      (description "Resistor  0R 100mW 0603")
      (fields
        (field (name "DISTRIBUTOR PART NUMBER") "RMCF0603ZT0R00CT-ND")
        (field (name "MANUFACTURER") "Stackpole Electronics Inc")
        (field (name "RESISTANCE") "0R")
      )
      (libsource (lib "MS IMP Library") (part "Res 0R 100mW 0603"))
    )
    (comp (ref "R13")
      (value "Resistor")
      (footprint "R0603L 0.45MM MS")
      (description "Resistor 1k 1% 125mW 0603")
      (fields
        (field (name "DISTRIBUTOR PART NUMBER") "MCT0603-1.00K-CFCT-ND")
        (field (name "MANUFACTURER") "Vishay Beyschlag/Draloric/BC Components")
        (field (name "RESISTANCE") "1k")
      )
      (libsource (lib "MS IMP Library") (part "Res 1k 1% 125mW 0603"))
    )
    (comp (ref "R14")
      (value "Resistor")
      (footprint "R0603L 0.45MM MS")
      (description "Resistor 1k5 1% 100mW 0603")
      (fields
        (field (name "DISTRIBUTOR PART NUMBER") "541-4020-1-ND")
        (field (name "MANUFACTURER") "Vishay Dale")
        (field (name "RESISTANCE") "1k5")
      )
      (libsource (lib "MS IMP Library") (part "Res 1k5 1% 100mW 0603 MS"))
    )
    (comp (ref "R15")
      (value "Resistor")
      (footprint "R0603L 0.45MM MS")
      (description "Resistor 1k 1% 125mW 0603")
      (fields
        (field (name "DISTRIBUTOR PART NUMBER") "MCT0603-1.00K-CFCT-ND")
        (field (name "MANUFACTURER") "Vishay Beyschlag/Draloric/BC Components")
        (field (name "RESISTANCE") "1k")
      )
      (libsource (lib "MS IMP Library") (part "Res 1k 1% 125mW 0603"))
    )
    (comp (ref "R16")
      (value "Resistor")
      (footprint "R0603L 0.45MM MS")
      (description "Resistor 49k9 1% 100mW 0603")
      (fields
        (field (name "DISTRIBUTOR PART NUMBER") "311-49.9KHRCT-ND")
        (field (name "MANUFACTURER") "Yageo")
        (field (name "RESISTANCE") "49k9")
      )
      (libsource (lib "MS IMP Library") (part "Res 49k9 1% 100mW 0603"))
    )
    (comp (ref "R17")
      (value "Resistor")
      (footprint "R0603L 0.45MM MS")
      (description "Resistor 47k 1% 100mW 0603")
      (fields
        (field (name "DISTRIBUTOR PART NUMBER") "YAG3355CT-ND")
        (field (name "MANUFACTURER") "Yageo")
        (field (name "RESISTANCE") "47k")
      )
      (libsource (lib "MS IMP Library") (part "Res 47k 1% 100mW 0603 MS"))
    )
    (comp (ref "R18")
      (value "Resistor")
      (footprint "0805 R 0.5mm MS")
      (description "Resistor  0R 125mW 0805")
      (fields
        (field (name "DISTRIBUTOR PART NUMBER") "311-0.0ARCT-ND")
        (field (name "MANUFACTURER") "Yageo")
        (field (name "RESISTANCE") "0R")
      )
      (libsource (lib "MS IMP Library") (part "Res 0R 125mW 0805"))
    )
    (comp (ref "R19")
      (value "Resistor")
      (footprint "0805 R 0.5mm MS")
      (description "Resistor  0R 125mW 0805")
      (fields
        (field (name "DISTRIBUTOR PART NUMBER") "311-0.0ARCT-ND")
        (field (name "MANUFACTURER") "Yageo")
        (field (name "RESISTANCE") "0R")
      )
      (libsource (lib "MS IMP Library") (part "Res 0R 125mW 0805"))
    )
    (comp (ref "R20")
      (value "Resistor")
      (footprint "2512 R 0.7mm MS")
      (description "Resistor 0.01R 1% 2W 2512")
      (fields
        (field (name "DISTRIBUTOR PART NUMBER") "YAG6033CT-ND")
        (field (name "MANUFACTURER") "Yageo")
        (field (name "RESISTANCE") "0.01R")
      )
      (libsource (lib "MS IMP Library") (part "Res 0.01R 1% 2W 2512 MS"))
    )
    (comp (ref "R21")
      (value "Resistor")
      (footprint "R0603L 0.45MM MS")
      (description "Resistor 47k 1% 100mW 0603")
      (fields
        (field (name "DISTRIBUTOR PART NUMBER") "YAG3355CT-ND")
        (field (name "MANUFACTURER") "Yageo")
        (field (name "RESISTANCE") "47k")
      )
      (libsource (lib "MS IMP Library") (part "Res 47k 1% 100mW 0603 MS"))
    )
    (comp (ref "R23")
      (value "Resistor")
      (footprint "R0603L 0.45MM MS")
      (description "Resistor 2k2 1% 100mW 0603")
      (fields
        (field (name "DISTRIBUTOR PART NUMBER") "311-2.20KHRCT-ND")
        (field (name "MANUFACTURER") "Yageo")
        (field (name "RESISTANCE") "2k2")
      )
      (libsource (lib "MS IMP Library") (part "Res 2k2 1% 100mW 0603 MS Pt02"))
    )
    (comp (ref "R25")
      (value "Resistor")
      (footprint "R0603L 0.45MM MS")
      (description "Resistor 1R 1% 100mW 0603")
      (fields
        (field (name "DISTRIBUTOR PART NUMBER") "311-1.00HRCT-ND")
        (field (name "MANUFACTURER") "Stackpole Electronics Inc")
        (field (name "RESISTANCE") "1R")
      )
      (libsource (lib "MS IMP Library") (part "Res 1R 1% 100mW 0603 MS"))
    )
    (comp (ref "R26")
      (value "Resistor")
      (footprint "R0603L 0.45MM MS")
      (description "Resistor 1R 1% 100mW 0603")
      (fields
        (field (name "DISTRIBUTOR PART NUMBER") "311-1.00HRCT-ND")
        (field (name "MANUFACTURER") "Stackpole Electronics Inc")
        (field (name "RESISTANCE") "1R")
      )
      (libsource (lib "MS IMP Library") (part "Res 1R 1% 100mW 0603 MS"))
    )
    (comp (ref "R27")
      (value "Resistor")
      (footprint "R0603L 0.45MM MS")
      (description "Resistor 2k2 1% 100mW 0603")
      (fields
        (field (name "DISTRIBUTOR PART NUMBER") "311-2.20KHRCT-ND")
        (field (name "MANUFACTURER") "Yageo")
        (field (name "RESISTANCE") "2k2")
      )
      (libsource (lib "MS IMP Library") (part "Res 2k2 1% 100mW 0603 MS Pt02"))
    )
    (comp (ref "R29")
      (value "Resistor")
      (footprint "R0603L 0.45MM MS")
      (description "Resistor 1k5 1% 100mW 0603")
      (fields
        (field (name "DISTRIBUTOR PART NUMBER") "541-4020-1-ND")
        (field (name "MANUFACTURER") "Vishay Dale")
        (field (name "RESISTANCE") "1k5")
      )
      (libsource (lib "MS IMP Library") (part "Res 1k5 1% 100mW 0603 MS"))
    )
    (comp (ref "R30")
      (value "Resistor")
      (footprint "R0603L 0.45MM MS")
      (description "Resistor 1k 1% 125mW 0603")
      (fields
        (field (name "DISTRIBUTOR PART NUMBER") "MCT0603-1.00K-CFCT-ND")
        (field (name "MANUFACTURER") "Vishay Beyschlag/Draloric/BC Components")
        (field (name "RESISTANCE") "1k")
      )
      (libsource (lib "MS IMP Library") (part "Res 1k 1% 125mW 0603"))
    )
    (comp (ref "R33")
      (value "Resistor")
      (footprint "R0603L 0.45MM MS")
      (description "Resistor  0R 100mW 0603")
      (fields
        (field (name "DISTRIBUTOR PART NUMBER") "RMCF0603ZT0R00CT-ND")
        (field (name "MANUFACTURER") "Stackpole Electronics Inc")
        (field (name "RESISTANCE") "0R")
      )
      (libsource (lib "MS IMP Library") (part "Res 0R 100mW 0603"))
    )
    (comp (ref "R35")
      (value "Resistor")
      (footprint "R0603L 0.45MM MS")
      (description "Resistor  0R 100mW 0603")
      (fields
        (field (name "DISTRIBUTOR PART NUMBER") "RMCF0603ZT0R00CT-ND")
        (field (name "MANUFACTURER") "Stackpole Electronics Inc")
        (field (name "RESISTANCE") "0R")
      )
      (libsource (lib "MS IMP Library") (part "Res 0R 100mW 0603"))
    )
    (comp (ref "R36")
      (value "Resistor")
      (footprint "R0603L 0.45MM MS")
      (description "Resistor 330R 1% 100mW 0603")
      (fields
        (field (name "DISTRIBUTOR PART NUMBER") "311-330HRCT-ND")
        (field (name "MANUFACTURER") "Yageo")
        (field (name "POPULATED") "DNP")
        (field (name "RESISTANCE") "330R")
      )
      (libsource (lib "MS IMP Library") (part "Res 330R 1% 100mW 0603 MS"))
    )
    (comp (ref "R37")
      (value "Resistor")
      (footprint "R0603L 0.45MM MS")
      (description "Resistor 22k 1% 100mW 0603")
      (fields
        (field (name "DISTRIBUTOR PART NUMBER") "541-4036-1-ND")
        (field (name "MANUFACTURER") "Vishay Dale")
        (field (name "POPULATED") "DNP")
        (field (name "RESISTANCE") "22k")
      )
      (libsource (lib "MS IMP Library") (part "Res 22k 1% 100mW 0603"))
    )
    (comp (ref "R38")
      (value "Resistor")
      (footprint "1206 R 0.6mm MS")
      (description "Resistor 10R 1% 500mW 1206")
      (fields
        (field (name "DISTRIBUTOR PART NUMBER") "RNCP1206FTD10R0CT-ND")
        (field (name "MANUFACTURER") "Stackpole Electronics Inc")
        (field (name "RESISTANCE") "10R")
      )
      (libsource (lib "MS IMP Library") (part "Res 10R 1% 500mW 1206"))
    )
    (comp (ref "R39")
      (value "Resistor")
      (footprint "2512 R 0.7mm MS")
      (description "Resistor 0R 1W 2512")
      (fields
        (field (name "DISTRIBUTOR PART NUMBER") "CR2512-J/-000ELFCT-ND")
        (field (name "MANUFACTURER") "Bourns Inc.")
        (field (name "POPULATED") "DNP")
        (field (name "RESISTANCE") "0R")
      )
      (libsource (lib "MS IMP Library") (part "Res 0R 1W 2512 MS"))
    )
    (comp (ref "R40")
      (value "Resistor")
      (footprint "2512 R 0.7mm MS")
      (description "Resistor 0R 1W 2512")
      (fields
        (field (name "DISTRIBUTOR PART NUMBER") "CR2512-J/-000ELFCT-ND")
        (field (name "MANUFACTURER") "Bourns Inc.")
        (field (name "POPULATED") "DNP")
        (field (name "RESISTANCE") "0R")
      )
      (libsource (lib "MS IMP Library") (part "Res 0R 1W 2512 MS"))
    )
    (comp (ref "R41")
      (value "Resistor")
      (footprint "R0603L 0.45MM MS")
      (description "Resistor 36k 1% 100mW 0603")
      (fields
        (field (name "DISTRIBUTOR PART NUMBER") "311-36.0KHRCT-ND")
        (field (name "MANUFACTURER") "Yageo")
        (field (name "RESISTANCE") "36k")
      )
      (libsource (lib "MS IMP Library") (part "Res 36k 1% 100mW 0603 MS Pt02"))
    )
    (comp (ref "R42")
      (value "Resistor")
      (footprint "2512 R 0.7mm MS")
      (description "Resistor 0.01R 1% 2W 2512")
      (fields
        (field (name "DISTRIBUTOR PART NUMBER") "YAG6033CT-ND")
        (field (name "MANUFACTURER") "Yageo")
        (field (name "POPULATED") "DNP")
        (field (name "RESISTANCE") "0.01R")
      )
      (libsource (lib "MS IMP Library") (part "Res 0.01R 1% 2W 2512 MS"))
    )
    (comp (ref "R43")
      (value "Resistor")
      (footprint "R0603L 0.45MM MS")
      (description "Resistor 1k 1% 125mW 0603")
      (fields
        (field (name "DISTRIBUTOR PART NUMBER") "MCT0603-1.00K-CFCT-ND")
        (field (name "MANUFACTURER") "Vishay Beyschlag/Draloric/BC Components")
        (field (name "RESISTANCE") "1k")
      )
      (libsource (lib "MS IMP Library") (part "Res 1k 1% 125mW 0603"))
    )
    (comp (ref "R59")
      (value "Resistor")
      (footprint "R0603L 0.45MM MS")
      (description "Resistor 47k 1% 100mW 0603")
      (fields
        (field (name "DISTRIBUTOR PART NUMBER") "YAG3355CT-ND")
        (field (name "MANUFACTURER") "Yageo")
        (field (name "RESISTANCE") "47k")
      )
      (libsource (lib "MS IMP Library") (part "Res 47k 1% 100mW 0603 MS"))
    )
    (comp (ref "R62")
      (value "Resistor")
      (footprint "R0603L 0.45MM MS")
      (description "Resistor 47k 1% 100mW 0603")
      (fields
        (field (name "DISTRIBUTOR PART NUMBER") "YAG3355CT-ND")
        (field (name "MANUFACTURER") "Yageo")
        (field (name "RESISTANCE") "47k")
      )
      (libsource (lib "MS IMP Library") (part "Res 47k 1% 100mW 0603 MS"))
    )
    (comp (ref "R79")
      (value "Resistor")
      (footprint "2512 R 0.7mm MS")
      (description "Resistor 1R 5% 1W 2512")
      (fields
        (field (name "DISTRIBUTOR PART NUMBER") "2019-SR733ATTE1R00FCT-ND")
        (field (name "MANUFACTURER") "KOA Speer Electronics, Inc.")
        (field (name "RESISTANCE") "1R")
      )
      (libsource (lib "MS IMP Library") (part "Res 1R 5% 1W 2512 MS"))
    )
    (comp (ref "R92")
      (value "Resistor")
      (footprint "R0603L 0.45MM MS")
      (description "Resistor 499k 1% 100mW 0603")
      (fields
        (field (name "DISTRIBUTOR PART NUMBER") "P499KHCT-ND")
        (field (name "MANUFACTURER") "Panasonic Electronic Components")
        (field (name "POPULATED") "DNP")
        (field (name "RESISTANCE") "499k")
      )
      (libsource (lib "MS IMP Library") (part "Res 499k 1% 100mW 0603 MS"))
    )
    (comp (ref "R93")
      (value "Resistor")
      (footprint "R0603L 0.45MM MS")
      (description "Resistor  0R 100mW 0603")
      (fields
        (field (name "DISTRIBUTOR PART NUMBER") "RMCF0603ZT0R00CT-ND")
        (field (name "MANUFACTURER") "Stackpole Electronics Inc")
        (field (name "RESISTANCE") "0R")
      )
      (libsource (lib "MS IMP Library") (part "Res 0R 100mW 0603"))
    )
    (comp (ref "R94")
      (value "Resistor")
      (footprint "R0603L 0.45MM MS")
      (description "Resistor  0R 100mW 0603")
      (fields
        (field (name "DISTRIBUTOR PART NUMBER") "RMCF0603ZT0R00CT-ND")
        (field (name "MANUFACTURER") "Stackpole Electronics Inc")
        (field (name "RESISTANCE") "0R")
      )
      (libsource (lib "MS IMP Library") (part "Res 0R 100mW 0603"))
    )
    (comp (ref "R95")
      (value "Inductor")
      (footprint "WE-TPC_5818/582892")
      (description "Inductor 5.3uH 2.3A 40 MOHM")
      (fields
        (field (name "DISTRIBUTOR PART NUMBER") "710-744053005")
        (field (name "MANUFACTURER") "Wurth Elektronik")
        (field (name "POPULATED") "DNP")
        (field (name "INDUCTANCE") "5.3uH")
      )
      (libsource (lib "MS IMP Library") (part "Ind 5.3uH 2.3A 2323  MS"))
    )
    (comp (ref "R96")
      (value "Resistor")
      (footprint "R0603L 0.45MM MS")
      (description "Resistor  0R 100mW 0603")
      (fields
        (field (name "DISTRIBUTOR PART NUMBER") "RMCF0603ZT0R00CT-ND")
        (field (name "MANUFACTURER") "Stackpole Electronics Inc")
        (field (name "RESISTANCE") "0R")
      )
      (libsource (lib "MS IMP Library") (part "Res 0R 100mW 0603"))
    )
    (comp (ref "R97")
      (value "Resistor")
      (footprint "R0603L 0.45MM MS")
      (description "Resistor  0R 100mW 0603")
      (fields
        (field (name "DISTRIBUTOR PART NUMBER") "RMCF0603ZT0R00CT-ND")
        (field (name "MANUFACTURER") "Stackpole Electronics Inc")
        (field (name "POPULATED") "DNP")
        (field (name "RESISTANCE") "0R")
      )
      (libsource (lib "MS IMP Library") (part "Res 0R 100mW 0603"))
    )
    (comp (ref "R98")
      (value "Resistor")
      (footprint "R0603L 0.45MM MS")
      (description "Resistor  0R 100mW 0603")
      (fields
        (field (name "DISTRIBUTOR PART NUMBER") "RMCF0603ZT0R00CT-ND")
        (field (name "MANUFACTURER") "Stackpole Electronics Inc")
        (field (name "POPULATED") "DNP")
        (field (name "RESISTANCE") "0R")
      )
      (libsource (lib "MS IMP Library") (part "Res 0R 100mW 0603"))
    )
    (comp (ref "R99")
      (value "Resistor")
      (footprint "R0603L 0.45MM MS")
      (description "Resistor 1k 1% 125mW 0603")
      (fields
        (field (name "DISTRIBUTOR PART NUMBER") "MCT0603-1.00K-CFCT-ND")
        (field (name "MANUFACTURER") "Vishay Beyschlag/Draloric/BC Components")
        (field (name "RESISTANCE") "1k")
      )
      (libsource (lib "MS IMP Library") (part "Res 1k 1% 125mW 0603"))
    )
    (comp (ref "R101")
      (value "Resistor")
      (footprint "R0603L 0.45MM MS")
      (description "Resistor 10k 1% 100mW 0603")
      (fields
        (field (name "DISTRIBUTOR PART NUMBER") "13-RC0603FR-1310KLCT-ND")
        (field (name "MANUFACTURER") "Yageo")
        (field (name "RESISTANCE") "10k")
      )
      (libsource (lib "MS IMP Library") (part "Res 10k 1% 100mW 0603"))
    )
    (comp (ref "R119")
      (value "Resistor")
      (footprint "R0603L 0.45MM MS")
      (description "Resistor 100k 1% 100mW 0603")
      (fields
        (field (name "DISTRIBUTOR PART NUMBER") "RMCF0603FT100KCT-ND")
        (field (name "MANUFACTURER") "Stackpole Electronics Inc")
        (field (name "RESISTANCE") "100k")
      )
      (libsource (lib "MS IMP Library") (part "Res 100k 1% 100mW 0603 Pt02"))
    )
    (comp (ref "R121")
      (value "Resistor")
      (footprint "R0603L 0.45MM MS")
      (description "Resistor 100k 1% 100mW 0603")
      (fields
        (field (name "DISTRIBUTOR PART NUMBER") "RMCF0603FT100KCT-ND")
        (field (name "MANUFACTURER") "Stackpole Electronics Inc")
        (field (name "RESISTANCE") "100k")
      )
      (libsource (lib "MS IMP Library") (part "Res 100k 1% 100mW 0603 Pt02"))
    )
    (comp (ref "R122")
      (value "Resistor")
      (footprint "R0603L 0.45MM MS")
      (description "Resistor 100R 1% 100mW 0603")
      (fields
        (field (name "DISTRIBUTOR PART NUMBER") "RMCF0603FT100RCT-ND")
        (field (name "MANUFACTURER") "Stackpole Electronics Inc")
        (field (name "RESISTANCE") "100R")
      )
      (libsource (lib "MS IMP Library") (part "Res 100R 1% 100mW 0603 MS Pt02"))
    )
    (comp (ref "SW1")
      (value "Switch")
      (footprint "SWITCH_HOLES")
      (description "Rocker Switch 16A 125V")
      (fields (field (name "DISTRIBUTOR PART NUMBER") "CKN11830-ND") (field (name "MANUFACTURER") "C&K"))
      (libsource (lib "MS IMP Library") (part "El-Mech Switch DF52J12P215HQA MS"))
    )
    (comp (ref "TP1")
      (value "+24V_FUSE")
      (footprint "TP SMD 1.2mm MS")
      (description "Test Point SMD 1.2 mm No Via")
      (libsource (lib "MS IMP Library") (part "Test Point SMD"))
    )
    (comp (ref "TP3")
      (value "+24V_+IN")
      (footprint "TP SMD 1.2mm MS")
      (description "Test Point SMD 1.2 mm No Via")
      (libsource (lib "MS IMP Library") (part "Test Point SMD"))
    )
    (comp (ref "TP4")
      (value "+15V_DCDC")
      (footprint "TP SMD 1.2mm MS")
      (description "Test Point SMD 1.2 mm No Via")
      (libsource (lib "MS IMP Library") (part "Test Point SMD"))
    )
    (comp (ref "TP5")
      (value "+15V_LC")
      (footprint "TP SMD 1.2mm MS")
      (description "Test Point SMD 1.2 mm No Via")
      (libsource (lib "MS IMP Library") (part "Test Point SMD"))
    )
    (comp (ref "TP6")
      (value "GND_-IN")
      (footprint "TP SMD 1.2mm MS")
      (description "Test Point SMD 1.2 mm No Via")
      (libsource (lib "MS IMP Library") (part "Test Point SMD"))
    )
    (comp (ref "TP7")
      (value "GND_24V")
      (footprint "TP SMD 1.2mm MS")
      (description "Test Point SMD 1.2 mm No Via")
      (libsource (lib "MS IMP Library") (part "Test Point SMD"))
    )
    (comp (ref "TP8")
      (value "GND")
      (footprint "TP SMD 1.2mm MS")
      (description "Test Point SMD 1.2 mm No Via")
      (libsource (lib "MS IMP Library") (part "Test Point SMD"))
    )
    (comp (ref "TP9")
      (value "+15V_OUT")
      (footprint "TP SMD 1.2mm MS")
      (description "Test Point SMD 1.2 mm No Via")
      (libsource (lib "MS IMP Library") (part "Test Point SMD"))
    )
    (comp (ref "TP10")
      (value "+15V")
      (footprint "TP SMD 1.2mm MS")
      (description "Test Point SMD 1.2 mm No Via")
      (libsource (lib "MS IMP Library") (part "Test Point SMD"))
    )
    (comp (ref "TP11")
      (value "GATE")
      (footprint "TP SMD 1.2mm MS")
      (description "Test Point SMD 1.2 mm No Via")
      (libsource (lib "MS IMP Library") (part "Test Point SMD"))
    )
    (comp (ref "TP13")
      (value "SDA_PWR")
      (footprint "TP SMD 1.2mm MS")
      (description "Test Point SMD 1.2 mm No Via")
      (libsource (lib "MS IMP Library") (part "Test Point SMD"))
    )
    (comp (ref "TP14")
      (value "SCL_PWR")
      (footprint "TP SMD 1.2mm MS")
      (description "Test Point SMD 1.2 mm No Via")
      (libsource (lib "MS IMP Library") (part "Test Point SMD"))
    )
    (comp (ref "U1")
      (value "DCM2322T50T1760T60")
      (footprint "DCM2322 MS")
      (description "Isolated Module DC DC Converter 1 Output 15V  4A  9V - 50V Input")
      (fields
        (field (name "DISTRIBUTOR PART NUMBER") "1102-DCM2322T50T1760T60-ND")
        (field (name "MANUFACTURER") "Vicor Corporation")
        (field (name "MANUFACTURER PART NUMBER") "DCM2322T50T1760T60")
      )
      (libsource (lib "MS IMP Library") (part "DC/DC 24V{colon}15V 50W DCM2322T50T1760T60 MS"))
    )
    (comp (ref "U2")
      (value "LTV817S")
      (footprint "LTV814S")
      (description "Optocoupler 5KV Transistor 4-SMD")
      (fields
        (field (name "DISTRIBUTOR PART NUMBER") "160-1367-5-ND")
        (field (name "MANUFACTURER") "Lite-On Inc.")
      )
      (libsource (lib "MS IMP Library") (part "IC LTV817S"))
    )
    (comp (ref "U3")
      (value "INA231BIYFDT")
      (footprint "DSBGA-12")
      (description "IC MONITOR PWR/CURR BIDIR 10MSOP")
      (fields
        (field (name "DISTRIBUTOR PART NUMBER") "595-INA231BIYFDT")
        (field (name "MANUFACTURER") "Texas Instruments")
      )
      (libsource (lib "MS IMP Library") (part "IC INA231BIYFDT MS"))
    )
    (comp (ref "U4")
      (value "LTV817S")
      (footprint "LTV814S")
      (description "Optocoupler 5KV Transistor 4-SMD")
      (fields
        (field (name "DISTRIBUTOR PART NUMBER") "160-1367-5-ND")
        (field (name "MANUFACTURER") "Lite-On Inc.")
      )
      (libsource (lib "MS IMP Library") (part "IC LTV817S"))
    )
    (comp (ref "U6")
      (value "TPS2410RMSR")
      (footprint "QFN50P250X250X60-14N")
      (description "IC OR CTRLR N+1 UQFN")
      (fields
        (field (name "DISTRIBUTOR PART NUMBER") "595-TPS2410RMSR")
        (field (name "MANUFACTURER") "Texas Instruments")
      )
      (libsource (lib "MS IMP Library") (part "IC TPS2410RMSR MS"))
    )
  )
  (nets
    (net (code "1") (name "+3V3") (class "Default")
      (node (ref "C48") (pin "1") (pinfunction "1_1") (pintype "passive"))
      (node (ref "LED4") (pin "A") (pinfunction "A_A") (pintype "passive"))
      (node (ref "R13") (pin "2") (pinfunction "2_2") (pintype "passive"))
      (node (ref "R15") (pin "1") (pinfunction "1_1") (pintype "passive"))
      (node (ref "R17") (pin "2") (pinfunction "2_2") (pintype "passive"))
      (node (ref "R21") (pin "2") (pinfunction "2_2") (pintype "passive"))
      (node (ref "R23") (pin "2") (pinfunction "2_2") (pintype "passive"))
      (node (ref "R27") (pin "2") (pinfunction "2_2") (pintype "passive"))
      (node (ref "R59") (pin "2") (pinfunction "2_2") (pintype "passive"))
      (node (ref "R62") (pin "2") (pinfunction "2_2") (pintype "passive"))
      (node (ref "U3") (pin "B1") (pinfunction "VS_B1") (pintype "power_in"))
    )
    (net (code "2") (name "+15V") (class "Default")
      (node (ref "C52") (pin "2") (pinfunction "2_2") (pintype "passive"))
      (node (ref "C53") (pin "1") (pinfunction "1_1") (pintype "passive"))
      (node (ref "Q1") (pin "1") (pinfunction "S_1") (pintype "passive"))
      (node (ref "Q1") (pin "2") (pinfunction "S_2") (pintype "passive"))
      (node (ref "Q1") (pin "3") (pinfunction "S_3") (pintype "passive"))
      (node (ref "R12") (pin "2") (pinfunction "2_2") (pintype "passive"))
      (node (ref "R19") (pin "2") (pinfunction "2_2") (pintype "passive"))
      (node (ref "R20") (pin "2") (pinfunction "2_2") (pintype "passive"))
      (node (ref "R38") (pin "2") (pinfunction "2_2") (pintype "passive"))
      (node (ref "R39") (pin "1") (pinfunction "1_1") (pintype "passive"))
      (node (ref "R40") (pin "1") (pinfunction "1_1") (pintype "passive"))
      (node (ref "R42") (pin "2") (pinfunction "2_2") (pintype "passive"))
      (node (ref "R92") (pin "2") (pinfunction "2_2") (pintype "passive"))
      (node (ref "R96") (pin "2") (pinfunction "2_2") (pintype "passive"))
      (node (ref "TP10") (pin "1") (pinfunction "1_1") (pintype "passive"))
      (node (ref "U3") (pin "D1") (pinfunction "VBUS_D1") (pintype "passive"))
      (node (ref "U6") (pin "13") (pinfunction "A_13") (pintype "passive"))
    )
    (net (code "3") (name "+15V_DCDC") (class "Default")
      (node (ref "C14") (pin "1") (pinfunction "1_1") (pintype "passive"))
      (node (ref "C19") (pin "2") (pinfunction "2_2") (pintype "passive"))
      (node (ref "C20") (pin "2") (pinfunction "2_2") (pintype "passive"))
      (node (ref "C24") (pin "1") (pinfunction "1_1") (pintype "passive"))
      (node (ref "C25") (pin "1") (pinfunction "1_1") (pintype "passive"))
      (node (ref "C26") (pin "1") (pinfunction "1_1") (pintype "passive"))
      (node (ref "C27") (pin "1") (pinfunction "1_1") (pintype "passive"))
      (node (ref "C28") (pin "1") (pinfunction "1_1") (pintype "passive"))
      (node (ref "D10") (pin "K") (pinfunction "K_K") (pintype "passive"))
      (node (ref "L5") (pin "1") (pinfunction "1_1") (pintype "passive"))
      (node (ref "L6") (pin "1") (pinfunction "1_1") (pintype "passive"))
      (node (ref "TP4") (pin "1") (pinfunction "1_1") (pintype "passive"))
      (node (ref "U1") (pin "A2") (pinfunction "+OUT_1_A2") (pintype "passive"))
      (node (ref "U1") (pin "C2") (pinfunction "+OUT_2_C2") (pintype "passive"))
    )
    (net (code "4") (name "+15V_LC") (class "Default")
      (node (ref "C38") (pin "1") (pinfunction "1_1") (pintype "passive"))
      (node (ref "C39") (pin "1") (pinfunction "1_1") (pintype "passive"))
      (node (ref "C40") (pin "1") (pinfunction "1_1") (pintype "passive"))
      (node (ref "C41") (pin "1") (pinfunction "1_1") (pintype "passive"))
      (node (ref "C42") (pin "1") (pinfunction "1_1") (pintype "passive"))
      (node (ref "C43") (pin "1") (pinfunction "1_1") (pintype "passive"))
      (node (ref "C44") (pin "1") (pinfunction "1_1") (pintype "passive"))
      (node (ref "C45") (pin "1") (pinfunction "1_1") (pintype "passive"))
      (node (ref "L6") (pin "2") (pinfunction "2_2") (pintype "passive"))
      (node (ref "R1") (pin "2") (pinfunction "2_2") (pintype "passive"))
      (node (ref "R18") (pin "2") (pinfunction "2_2") (pintype "passive"))
      (node (ref "R20") (pin "1") (pinfunction "1_1") (pintype "passive"))
      (node (ref "R42") (pin "1") (pinfunction "1_1") (pintype "passive"))
      (node (ref "TP5") (pin "1") (pinfunction "1_1") (pintype "passive"))
    )
    (net (code "5") (name "+15V_OUT") (class "Default")
      (node (ref "Q1") (pin "5") (pinfunction "D_5") (pintype "passive"))
      (node (ref "Q1") (pin "6") (pinfunction "D_6") (pintype "passive"))
      (node (ref "Q1") (pin "7") (pinfunction "D_7") (pintype "passive"))
      (node (ref "Q1") (pin "8") (pinfunction "D_8") (pintype "passive"))
      (node (ref "R30") (pin "2") (pinfunction "2_2") (pintype "passive"))
      (node (ref "R39") (pin "2") (pinfunction "2_2") (pintype "passive"))
      (node (ref "R40") (pin "2") (pinfunction "2_2") (pintype "passive"))
      (node (ref "TP9") (pin "1") (pinfunction "1_1") (pintype "passive"))
      (node (ref "U6") (pin "12") (pinfunction "C_12") (pintype "passive"))
    )
    (net (code "6") (name "+24V") (class "Default")
      (node (ref "+24V") (pin "1") (pinfunction "1_1") (pintype "passive"))
      (node (ref "J1") (pin "1") (pinfunction "1_1") (pintype "passive"))
      (node (ref "MOV1") (pin "2") (pinfunction "2_2") (pintype "passive"))
      (node (ref "SW1") (pin "1") (pinfunction "1_1") (pintype "passive"))
    )
    (net (code "7") (name "+24V_+IN") (class "Default")
      (node (ref "C10") (pin "1") (pinfunction "1_1") (pintype "passive"))
      (node (ref "C11") (pin "1") (pinfunction "1_1") (pintype "passive"))
      (node (ref "C12") (pin "1") (pinfunction "1_1") (pintype "passive"))
      (node (ref "C17") (pin "1") (pinfunction "1_1") (pintype "passive"))
      (node (ref "C18") (pin "2") (pinfunction "2_2") (pintype "passive"))
      (node (ref "C21") (pin "1") (pinfunction "1_1") (pintype "passive"))
      (node (ref "C22") (pin "1") (pinfunction "1_1") (pintype "passive"))
      (node (ref "C23") (pin "1") (pinfunction "1_1") (pintype "passive"))
      (node (ref "C7") (pin "1") (pinfunction "1_1") (pintype "passive"))
      (node (ref "C8") (pin "1") (pinfunction "1_1") (pintype "passive"))
      (node (ref "C9") (pin "1") (pinfunction "1_1") (pintype "passive"))
      (node (ref "L3") (pin "2") (pinfunction "2_2") (pintype "passive"))
      (node (ref "R2") (pin "2") (pinfunction "2_2") (pintype "passive"))
      (node (ref "R3") (pin "1") (pinfunction "1_1") (pintype "passive"))
      (node (ref "R79") (pin "2") (pinfunction "2_2") (pintype "passive"))
      (node (ref "TP3") (pin "1") (pinfunction "1_1") (pintype "passive"))
      (node (ref "U1") (pin "A1") (pinfunction "+IN_A1") (pintype "passive"))
    )
    (net (code "8") (name "+24V_CMCK") (class "Default")
      (node (ref "D11") (pin "K") (pinfunction "K_K") (pintype "passive"))
      (node (ref "L2") (pin "10") (pinfunction "10_10") (pintype "passive"))
      (node (ref "L2") (pin "9") (pinfunction "9_9") (pintype "passive"))
      (node (ref "L3") (pin "1") (pinfunction "1_1") (pintype "passive"))
      (node (ref "R95") (pin "1") (pinfunction "1_1") (pintype "passive"))
      (node (ref "R99") (pin "1") (pinfunction "1_1") (pintype "passive"))
    )
    (net (code "9") (name "+24V_DIO") (class "Default")
      (node (ref "D1") (pin "K") (pinfunction "K_K") (pintype "passive"))
      (node (ref "D2") (pin "1") (pinfunction "K_1") (pintype "passive"))
      (node (ref "F1") (pin "1") (pinfunction "1_1") (pintype "passive"))
    )
    (net (code "10") (name "+24V_FIL_L") (class "Default")
      (node (ref "R2") (pin "1") (pinfunction "1_1") (pintype "passive"))
      (node (ref "R79") (pin "1") (pinfunction "1_1") (pintype "passive"))
      (node (ref "R95") (pin "2") (pinfunction "2_2") (pintype "passive"))
    )
    (net (code "11") (name "+24V_FUSE") (class "Default")
      (node (ref "C15") (pin "2") (pinfunction "2_2") (pintype "passive"))
      (node (ref "C16") (pin "2") (pinfunction "2_2") (pintype "passive"))
      (node (ref "C29") (pin "1") (pinfunction "1_1") (pintype "passive"))
      (node (ref "F1") (pin "2") (pinfunction "2_2") (pintype "passive"))
      (node (ref "L2") (pin "1") (pinfunction "1_1") (pintype "passive"))
      (node (ref "L2") (pin "2") (pinfunction "2_2") (pintype "passive"))
      (node (ref "TP1") (pin "1") (pinfunction "1_1") (pintype "passive"))
    )
    (net (code "12") (name "+24V_L") (class "Default")
      (node (ref "D2") (pin "2") (pinfunction "A_2") (pintype "passive"))
      (node (ref "L1") (pin "2") (pinfunction "2_2") (pintype "passive"))
    )
    (net (code "13") (name "+24V_SW") (class "Default")
      (node (ref "L1") (pin "1") (pinfunction "1_1") (pintype "passive"))
      (node (ref "SW1") (pin "2") (pinfunction "2_2") (pintype "passive"))
    )
    (net (code "14") (name "/+In") (class "Default")
      (node (ref "C46") (pin "1") (pinfunction "1_1") (pintype "passive"))
      (node (ref "R25") (pin "1") (pinfunction "1_1") (pintype "passive"))
      (node (ref "U3") (pin "D3") (pinfunction "IN+_D3") (pintype "input"))
    )
    (net (code "15") (name "/-In") (class "Default")
      (node (ref "C46") (pin "2") (pinfunction "2_2") (pintype "passive"))
      (node (ref "R26") (pin "1") (pinfunction "1_1") (pintype "passive"))
      (node (ref "U3") (pin "D2") (pinfunction "IN-_D2") (pintype "input"))
    )
    (net (code "16") (name "/BLEEDER_ON_OFF") (class "Default")
      (node (ref "R10") (pin "2") (pinfunction "2_2") (pintype "passive"))
      (node (ref "R11") (pin "2") (pinfunction "2_2") (pintype "passive"))
      (node (ref "R12") (pin "1") (pinfunction "1_1") (pintype "passive"))
      (node (ref "R5") (pin "2") (pinfunction "2_2") (pintype "passive"))
      (node (ref "R6") (pin "2") (pinfunction "2_2") (pintype "passive"))
      (node (ref "R7") (pin "2") (pinfunction "2_2") (pintype "passive"))
      (node (ref "R8") (pin "2") (pinfunction "2_2") (pintype "passive"))
      (node (ref "R9") (pin "2") (pinfunction "2_2") (pintype "passive"))
      (node (ref "R96") (pin "1") (pinfunction "1_1") (pintype "passive"))
      (node (ref "R97") (pin "1") (pinfunction "1_1") (pintype "passive"))
      (node (ref "R98") (pin "1") (pinfunction "1_1") (pintype "passive"))
    )
    (net (code "17") (name "/EN") (class "Default")
      (node (ref "R35") (pin "1") (pinfunction "1_1") (pintype "passive"))
      (node (ref "U1") (pin "C1") (pinfunction "EN_C1") (pintype "passive"))
    )
    (net (code "18") (name "/FT") (class "Default")
      (node (ref "R14") (pin "2") (pinfunction "2_2") (pintype "passive"))
      (node (ref "U1") (pin "D1") (pinfunction "FT_D1") (pintype "passive"))
    )
    (net (code "19") (name "/GATE") (class "Default")
      (node (ref "Q1") (pin "4") (pinfunction "G_4") (pintype "passive"))
      (node (ref "TP11") (pin "1") (pinfunction "1_1") (pintype "passive"))
      (node (ref "U6") (pin "10") (pinfunction "GATE_10") (pintype "passive"))
    )
    (net (code "20") (name "/LED_PWR_OK") (class "Default") (node (ref "Q2") (pin "1") (pintype "passive")))
    (net (code "21") (name "/OV") (class "Default")
      (node (ref "R93") (pin "1") (pinfunction "1_1") (pintype "passive"))
      (node (ref "R94") (pin "2") (pinfunction "2_2") (pintype "passive"))
      (node (ref "U6") (pin "7") (pinfunction "OV_7") (pintype "passive"))
    )
    (net (code "22") (name "/SCL") (class "Default")
      (node (ref "R27") (pin "1") (pinfunction "1_1") (pintype "passive"))
      (node (ref "TP14") (pin "1") (pinfunction "1_1") (pintype "passive"))
      (node (ref "U3") (pin "A1") (pinfunction "SCL_A1") (pintype "passive"))
    )
    (net (code "23") (name "/SDA") (class "Default")
      (node (ref "R23") (pin "1") (pinfunction "1_1") (pintype "passive"))
      (node (ref "TP13") (pin "1") (pinfunction "1_1") (pintype "passive"))
      (node (ref "U3") (pin "A2") (pinfunction "SDA_A2") (pintype "passive"))
    )
    (net (code "24") (name "/STAT") (class "Default")
      (node (ref "U6") (pin "5") (pinfunction "STAT_5") (pintype "passive"))
    )
    (net (code "25") (name "/TR") (class "Default")
      (node (ref "R36") (pin "2") (pinfunction "2_2") (pintype "passive"))
      (node (ref "U1") (pin "B1") (pinfunction "TR_B1") (pintype "passive"))
    )
    (net (code "26") (name "/UV") (class "Default")
      (node (ref "R92") (pin "1") (pinfunction "1_1") (pintype "passive"))
      (node (ref "R93") (pin "2") (pinfunction "2_2") (pintype "passive"))
      (node (ref "U6") (pin "8") (pinfunction "UV_8") (pintype "passive"))
    )
    (net (code "27") (name "/{slash}24V_PRESENT") (class "Default")
      (node (ref "LED1") (pin "K") (pinfunction "K_K") (pintype "passive"))
      (node (ref "R15") (pin "2") (pinfunction "2_2") (pintype "passive"))
      (node (ref "U4") (pin "4") (pinfunction "Collector_4") (pintype "passive"))
    )
    (net (code "28") (name "/{slash}ALERT_PWR") (class "Default")
      (node (ref "R21") (pin "1") (pinfunction "1_1") (pintype "passive"))
      (node (ref "U3") (pin "A3") (pinfunction "ALERT_A3") (pintype "open_collector"))
    )
    (net (code "29") (name "/{slash}FLTB") (class "Default")
      (node (ref "R17") (pin "1") (pinfunction "1_1") (pintype "passive"))
      (node (ref "U6") (pin "6") (pinfunction "FLTB_6") (pintype "passive"))
    )
    (net (code "30") (name "/{slash}FT_VICOR") (class "Default")
      (node (ref "R62") (pin "1") (pinfunction "1_1") (pintype "passive"))
      (node (ref "U2") (pin "4") (pinfunction "Collector_4") (pintype "passive"))
    )
    (net (code "31") (name "/{slash}PWR_GOOD_TPS") (class "Default")
      (node (ref "R59") (pin "1") (pinfunction "1_1") (pintype "passive"))
      (node (ref "U6") (pin "2") (pinfunction "PG_2") (pintype "open_collector"))
    )
    (net (code "32") (name "GND") (class "Default")
      (node (ref "C15") (pin "1") (pinfunction "1_1") (pintype "passive"))
      (node (ref "C16") (pin "1") (pinfunction "1_1") (pintype "passive"))
      (node (ref "C17") (pin "2") (pinfunction "2_2") (pintype "passive"))
      (node (ref "C18") (pin "1") (pinfunction "1_1") (pintype "passive"))
      (node (ref "C19") (pin "1") (pinfunction "1_1") (pintype "passive"))
      (node (ref "C20") (pin "1") (pinfunction "1_1") (pintype "passive"))
      (node (ref "C24") (pin "2") (pinfunction "2_2") (pintype "passive"))
      (node (ref "C25") (pin "2") (pinfunction "2_2") (pintype "passive"))
      (node (ref "C26") (pin "2") (pinfunction "2_2") (pintype "passive"))
      (node (ref "C27") (pin "2") (pinfunction "2_2") (pintype "passive"))
      (node (ref "C28") (pin "2") (pinfunction "2_2") (pintype "passive"))
      (node (ref "C30") (pin "1") (pinfunction "1_1") (pintype "passive"))
      (node (ref "C30") (pin "2") (pinfunction "2_2") (pintype "passive"))
      (node (ref "C31") (pin "1") (pinfunction "1_1") (pintype "passive"))
      (node (ref "C31") (pin "2") (pinfunction "2_2") (pintype "passive"))
      (node (ref "C32") (pin "2") (pinfunction "2_2") (pintype "passive"))
      (node (ref "C33") (pin "2") (pinfunction "2_2") (pintype "passive"))
      (node (ref "C34") (pin "2") (pinfunction "2_2") (pintype "passive"))
      (node (ref "C35") (pin "2") (pinfunction "2_2") (pintype "passive"))
      (node (ref "C37") (pin "1") (pinfunction "1_1") (pintype "passive"))
      (node (ref "C38") (pin "2") (pinfunction "2_2") (pintype "passive"))
      (node (ref "C39") (pin "2") (pinfunction "2_2") (pintype "passive"))
      (node (ref "C40") (pin "2") (pinfunction "2_2") (pintype "passive"))
      (node (ref "C41") (pin "2") (pinfunction "2_2") (pintype "passive"))
      (node (ref "C42") (pin "2") (pinfunction "2_2") (pintype "passive"))
      (node (ref "C43") (pin "2") (pinfunction "2_2") (pintype "passive"))
      (node (ref "C44") (pin "2") (pinfunction "2_2") (pintype "passive"))
      (node (ref "C45") (pin "2") (pinfunction "2_2") (pintype "passive"))
      (node (ref "C48") (pin "2") (pinfunction "2_2") (pintype "passive"))
      (node (ref "C51") (pin "1") (pinfunction "1_1") (pintype "passive"))
      (node (ref "D10") (pin "A") (pinfunction "A_A") (pintype "passive"))
      (node (ref "D3") (pin "A") (pinfunction "A_A") (pintype "passive"))
      (node (ref "D4") (pin "A") (pinfunction "A_A") (pintype "passive"))
      (node (ref "HS1") (pin "1") (pinfunction "MTH1_1") (pintype "passive"))
      (node (ref "HS1") (pin "2") (pinfunction "MTH2_2") (pintype "passive"))
      (node (ref "HS1") (pin "3") (pinfunction "MTH3_3") (pintype "passive"))
      (node (ref "HS1") (pin "4") (pinfunction "MTH4_4") (pintype "passive"))
      (node (ref "J1") (pin "3") (pinfunction "3_3") (pintype "passive"))
      (node (ref "LED2") (pin "K") (pinfunction "K_K") (pintype "passive"))
      (node (ref "Q2") (pin "2") (pintype "passive"))
      (node (ref "R10") (pin "1") (pinfunction "1_1") (pintype "passive"))
      (node (ref "R11") (pin "1") (pinfunction "1_1") (pintype "passive"))
      (node (ref "R41") (pin "1") (pinfunction "1_1") (pintype "passive"))
      (node (ref "R5") (pin "1") (pinfunction "1_1") (pintype "passive"))
      (node (ref "R6") (pin "1") (pinfunction "1_1") (pintype "passive"))
      (node (ref "R7") (pin "1") (pinfunction "1_1") (pintype "passive"))
      (node (ref "R8") (pin "1") (pinfunction "1_1") (pintype "passive"))
      (node (ref "R9") (pin "1") (pinfunction "1_1") (pintype "passive"))
      (node (ref "R94") (pin "1") (pinfunction "1_1") (pintype "passive"))
      (node (ref "R97") (pin "2") (pinfunction "2_2") (pintype "passive"))
      (node (ref "R98") (pin "2") (pinfunction "2_2") (pintype "passive"))
      (node (ref "TP8") (pin "1") (pinfunction "1_1") (pintype "passive"))
      (node (ref "U1") (pin "B2") (pinfunction "-OUT_1_B2") (pintype "passive"))
      (node (ref "U1") (pin "D2") (pinfunction "-OUT_2_D2") (pintype "passive"))
      (node (ref "U2") (pin "3") (pinfunction "Emitter_3") (pintype "passive"))
      (node (ref "U3") (pin "B3") (pinfunction "A0_B3") (pintype "passive"))
      (node (ref "U3") (pin "C1") (pinfunction "GND_C1") (pintype "power_in"))
      (node (ref "U3") (pin "C3") (pinfunction "A1_C3") (pintype "passive"))
      (node (ref "U4") (pin "3") (pinfunction "Emitter_3") (pintype "passive"))
      (node (ref "U6") (pin "11") (pinfunction "RSVD_11") (pintype "passive"))
      (node (ref "U6") (pin "9") (pinfunction "GND_9") (pintype "passive"))
    )
    (net (code "33") (name "GND_-IN") (class "Default")
      (node (ref "C10") (pin "2") (pinfunction "2_2") (pintype "passive"))
      (node (ref "C11") (pin "2") (pinfunction "2_2") (pintype "passive"))
      (node (ref "C12") (pin "2") (pinfunction "2_2") (pintype "passive"))
      (node (ref "C21") (pin "2") (pinfunction "2_2") (pintype "passive"))
      (node (ref "C22") (pin "2") (pinfunction "2_2") (pintype "passive"))
      (node (ref "C23") (pin "2") (pinfunction "2_2") (pintype "passive"))
      (node (ref "C32") (pin "1") (pinfunction "1_1") (pintype "passive"))
      (node (ref "C33") (pin "1") (pinfunction "1_1") (pintype "passive"))
      (node (ref "C49") (pin "2") (pinfunction "2_2") (pintype "passive"))
      (node (ref "C50") (pin "2") (pinfunction "2_2") (pintype "passive"))
      (node (ref "C7") (pin "2") (pinfunction "2_2") (pintype "passive"))
      (node (ref "C8") (pin "2") (pinfunction "2_2") (pintype "passive"))
      (node (ref "C9") (pin "2") (pinfunction "2_2") (pintype "passive"))
      (node (ref "L2") (pin "6") (pinfunction "6_6") (pintype "passive"))
      (node (ref "L2") (pin "7") (pinfunction "7_7") (pintype "passive"))
      (node (ref "Q5") (pin "2") (pinfunction "E_2") (pintype "passive"))
      (node (ref "Q6") (pin "2") (pinfunction "S_2") (pintype "passive"))
      (node (ref "R119") (pin "1") (pinfunction "1_1") (pintype "passive"))
      (node (ref "R121") (pin "2") (pinfunction "2_2") (pintype "passive"))
      (node (ref "R16") (pin "1") (pinfunction "1_1") (pintype "passive"))
      (node (ref "R37") (pin "1") (pinfunction "1_1") (pintype "passive"))
      (node (ref "R4") (pin "1") (pinfunction "1_1") (pintype "passive"))
      (node (ref "TP6") (pin "1") (pinfunction "1_1") (pintype "passive"))
      (node (ref "U1") (pin "E1") (pinfunction "-IN_E1") (pintype "passive"))
      (node (ref "U2") (pin "2") (pinfunction "Cathode_2") (pintype "passive"))
      (node (ref "U4") (pin "2") (pinfunction "Cathode_2") (pintype "passive"))
    )
    (net (code "34") (name "GND_24V") (class "Default")
      (node (ref "C29") (pin "2") (pinfunction "2_2") (pintype "passive"))
      (node (ref "C34") (pin "1") (pinfunction "1_1") (pintype "passive"))
      (node (ref "C35") (pin "1") (pinfunction "1_1") (pintype "passive"))
      (node (ref "D1") (pin "A") (pinfunction "A_A") (pintype "passive"))
      (node (ref "J1") (pin "2") (pinfunction "2_2") (pintype "passive"))
      (node (ref "L2") (pin "4") (pinfunction "4_4") (pintype "passive"))
      (node (ref "L2") (pin "5") (pinfunction "5_5") (pintype "passive"))
      (node (ref "MOV1") (pin "1") (pinfunction "1_1") (pintype "passive"))
      (node (ref "TP7") (pin "1") (pinfunction "1_1") (pintype "passive"))
    )
    (net (code "35") (name "Net-(C13-Pad1)") (class "Default")
      (node (ref "C13") (pin "1") (pinfunction "1_1") (pintype "passive"))
      (node (ref "C14") (pin "2") (pinfunction "2_2") (pintype "passive"))
    )
    (net (code "36") (name "Net-(C13-Pad2)") (class "Default")
      (node (ref "C13") (pin "2") (pinfunction "2_2") (pintype "passive"))
      (node (ref "R3") (pin "2") (pinfunction "2_2") (pintype "passive"))
    )
    (net (code "37") (name "Net-(C36-Pad1)") (class "Default")
      (node (ref "C36") (pin "1") (pinfunction "1_1") (pintype "passive"))
      (node (ref "C37") (pin "2") (pinfunction "2_2") (pintype "passive"))
    )
    (net (code "38") (name "Net-(C36-Pad2)") (class "Default")
      (node (ref "C36") (pin "2") (pinfunction "2_2") (pintype "passive"))
      (node (ref "R4") (pin "2") (pinfunction "2_2") (pintype "passive"))
    )
    (net (code "39") (name "Net-(C49-Pad1)") (class "Default")
      (node (ref "C49") (pin "1") (pinfunction "1_1") (pintype "passive"))
      (node (ref "R33") (pin "2") (pinfunction "2_2") (pintype "passive"))
      (node (ref "R35") (pin "2") (pinfunction "2_2") (pintype "passive"))
    )
    (net (code "40") (name "Net-(C50-Pad1)") (class "Default")
      (node (ref "C50") (pin "1") (pinfunction "1_1") (pintype "passive"))
      (node (ref "R36") (pin "1") (pinfunction "1_1") (pintype "passive"))
      (node (ref "R37") (pin "2") (pinfunction "2_2") (pintype "passive"))
    )
    (net (code "41") (name "Net-(D3-PadK)") (class "Default")
      (node (ref "D3") (pin "K") (pinfunction "K_K") (pintype "passive"))
      (node (ref "FB2") (pin "1") (pinfunction "1_1") (pintype "passive"))
      (node (ref "R19") (pin "1") (pinfunction "1_1") (pintype "passive"))
    )
    (net (code "42") (name "Net-(D4-PadK)") (class "Default")
      (node (ref "D4") (pin "K") (pinfunction "K_K") (pintype "passive"))
      (node (ref "FB1") (pin "1") (pinfunction "1_1") (pintype "passive"))
      (node (ref "R18") (pin "1") (pinfunction "1_1") (pintype "passive"))
    )
    (net (code "43") (name "Net-(D11-PadA)") (class "Default")
      (node (ref "D11") (pin "A") (pinfunction "A_A") (pintype "passive"))
      (node (ref "R101") (pin "2") (pinfunction "2_2") (pintype "passive"))
      (node (ref "R29") (pin "2") (pinfunction "2_2") (pintype "passive"))
    )
    (net (code "44") (name "Net-(D12-PadA)") (class "Default")
      (node (ref "D12") (pin "A") (pinfunction "A_A") (pintype "passive"))
      (node (ref "LED2") (pin "A") (pinfunction "A_A") (pintype "passive"))
    )
    (net (code "45") (name "Net-(D12-PadK)") (class "Default")
      (node (ref "D12") (pin "K") (pinfunction "K_K") (pintype "passive"))
      (node (ref "R30") (pin "1") (pinfunction "1_1") (pintype "passive"))
    )
    (net (code "46") (name "Net-(FB1-Pad2)") (class "Default")
      (node (ref "FB1") (pin "2") (pinfunction "2_2") (pintype "passive"))
      (node (ref "R25") (pin "2") (pinfunction "2_2") (pintype "passive"))
    )
    (net (code "47") (name "Net-(FB2-Pad2)") (class "Default")
      (node (ref "FB2") (pin "2") (pinfunction "2_2") (pintype "passive"))
      (node (ref "R26") (pin "2") (pinfunction "2_2") (pintype "passive"))
    )
    (net (code "48") (name "Net-(L5-Pad2)") (class "Default")
      (node (ref "L5") (pin "2") (pinfunction "2_2") (pintype "passive"))
      (node (ref "R1") (pin "1") (pinfunction "1_1") (pintype "passive"))
    )
    (net (code "49") (name "Net-(LED1-PadA)") (class "Default")
      (node (ref "LED1") (pin "A") (pinfunction "A_A") (pintype "passive"))
      (node (ref "R13") (pin "1") (pinfunction "1_1") (pintype "passive"))
    )
    (net (code "50") (name "Net-(LED4-PadK)") (class "Default")
      (node (ref "LED4") (pin "K") (pinfunction "K_K") (pintype "passive"))
      (node (ref "R43") (pin "2") (pinfunction "2_2") (pintype "passive"))
    )
    (net (code "51") (name "Net-(Q2-Pad3)") (class "Default")
      (node (ref "Q2") (pin "3") (pintype "passive"))
      (node (ref "R43") (pin "1") (pinfunction "1_1") (pintype "passive"))
    )
    (net (code "52") (name "Net-(Q5-B)") (class "Default")
      (node (ref "Q5") (pin "1") (pinfunction "B_1") (pintype "passive"))
      (node (ref "R101") (pin "1") (pinfunction "1_1") (pintype "passive"))
      (node (ref "R119") (pin "2") (pinfunction "2_2") (pintype "passive"))
    )
    (net (code "53") (name "Net-(Q5-C)") (class "Default")
      (node (ref "Q5") (pin "3") (pinfunction "C_3") (pintype "passive"))
      (node (ref "R121") (pin "1") (pinfunction "1_1") (pintype "passive"))
      (node (ref "R122") (pin "1") (pinfunction "1_1") (pintype "passive"))
      (node (ref "R99") (pin "2") (pinfunction "2_2") (pintype "passive"))
    )
    (net (code "54") (name "Net-(Q6-D)") (class "Default")
      (node (ref "Q6") (pin "3") (pinfunction "D_3") (pintype "passive"))
      (node (ref "R33") (pin "1") (pinfunction "1_1") (pintype "passive"))
    )
    (net (code "55") (name "Net-(Q6-G)") (class "Default")
      (node (ref "Q6") (pin "1") (pinfunction "G_1") (pintype "passive"))
      (node (ref "R122") (pin "2") (pinfunction "2_2") (pintype "passive"))
    )
    (net (code "56") (name "Net-(U2-Anode)") (class "Default")
      (node (ref "R14") (pin "1") (pinfunction "1_1") (pintype "passive"))
      (node (ref "R16") (pin "2") (pinfunction "2_2") (pintype "passive"))
      (node (ref "U2") (pin "1") (pinfunction "Anode_1") (pintype "passive"))
    )
    (net (code "57") (name "Net-(U4-Anode)") (class "Default")
      (node (ref "R29") (pin "1") (pinfunction "1_1") (pintype "passive"))
      (node (ref "U4") (pin "1") (pinfunction "Anode_1") (pintype "passive"))
    )
    (net (code "58") (name "Net-(U6-BYP)") (class "Default")
      (node (ref "C52") (pin "1") (pinfunction "1_1") (pintype "passive"))
      (node (ref "U6") (pin "1") (pinfunction "BYP_1") (pintype "passive"))
    )
    (net (code "59") (name "Net-(U6-FLTR)") (class "Default")
      (node (ref "C53") (pin "2") (pinfunction "2_2") (pintype "passive"))
      (node (ref "U6") (pin "14") (pinfunction "FLTR_14") (pintype "passive"))
    )
    (net (code "60") (name "Net-(U6-RSET)") (class "Default")
      (node (ref "R41") (pin "2") (pinfunction "2_2") (pintype "passive"))
      (node (ref "U6") (pin "4") (pinfunction "RSET_4") (pintype "passive"))
    )
    (net (code "61") (name "Net-(U6-VDD)") (class "Default")
      (node (ref "C51") (pin "2") (pinfunction "2_2") (pintype "passive"))
      (node (ref "R38") (pin "1") (pinfunction "1_1") (pintype "passive"))
      (node (ref "U6") (pin "3") (pinfunction "VDD_3") (pintype "passive"))
    )
  )
)
